# schematic.net
KiCad netlist of a schematic drawn in Altium Designer
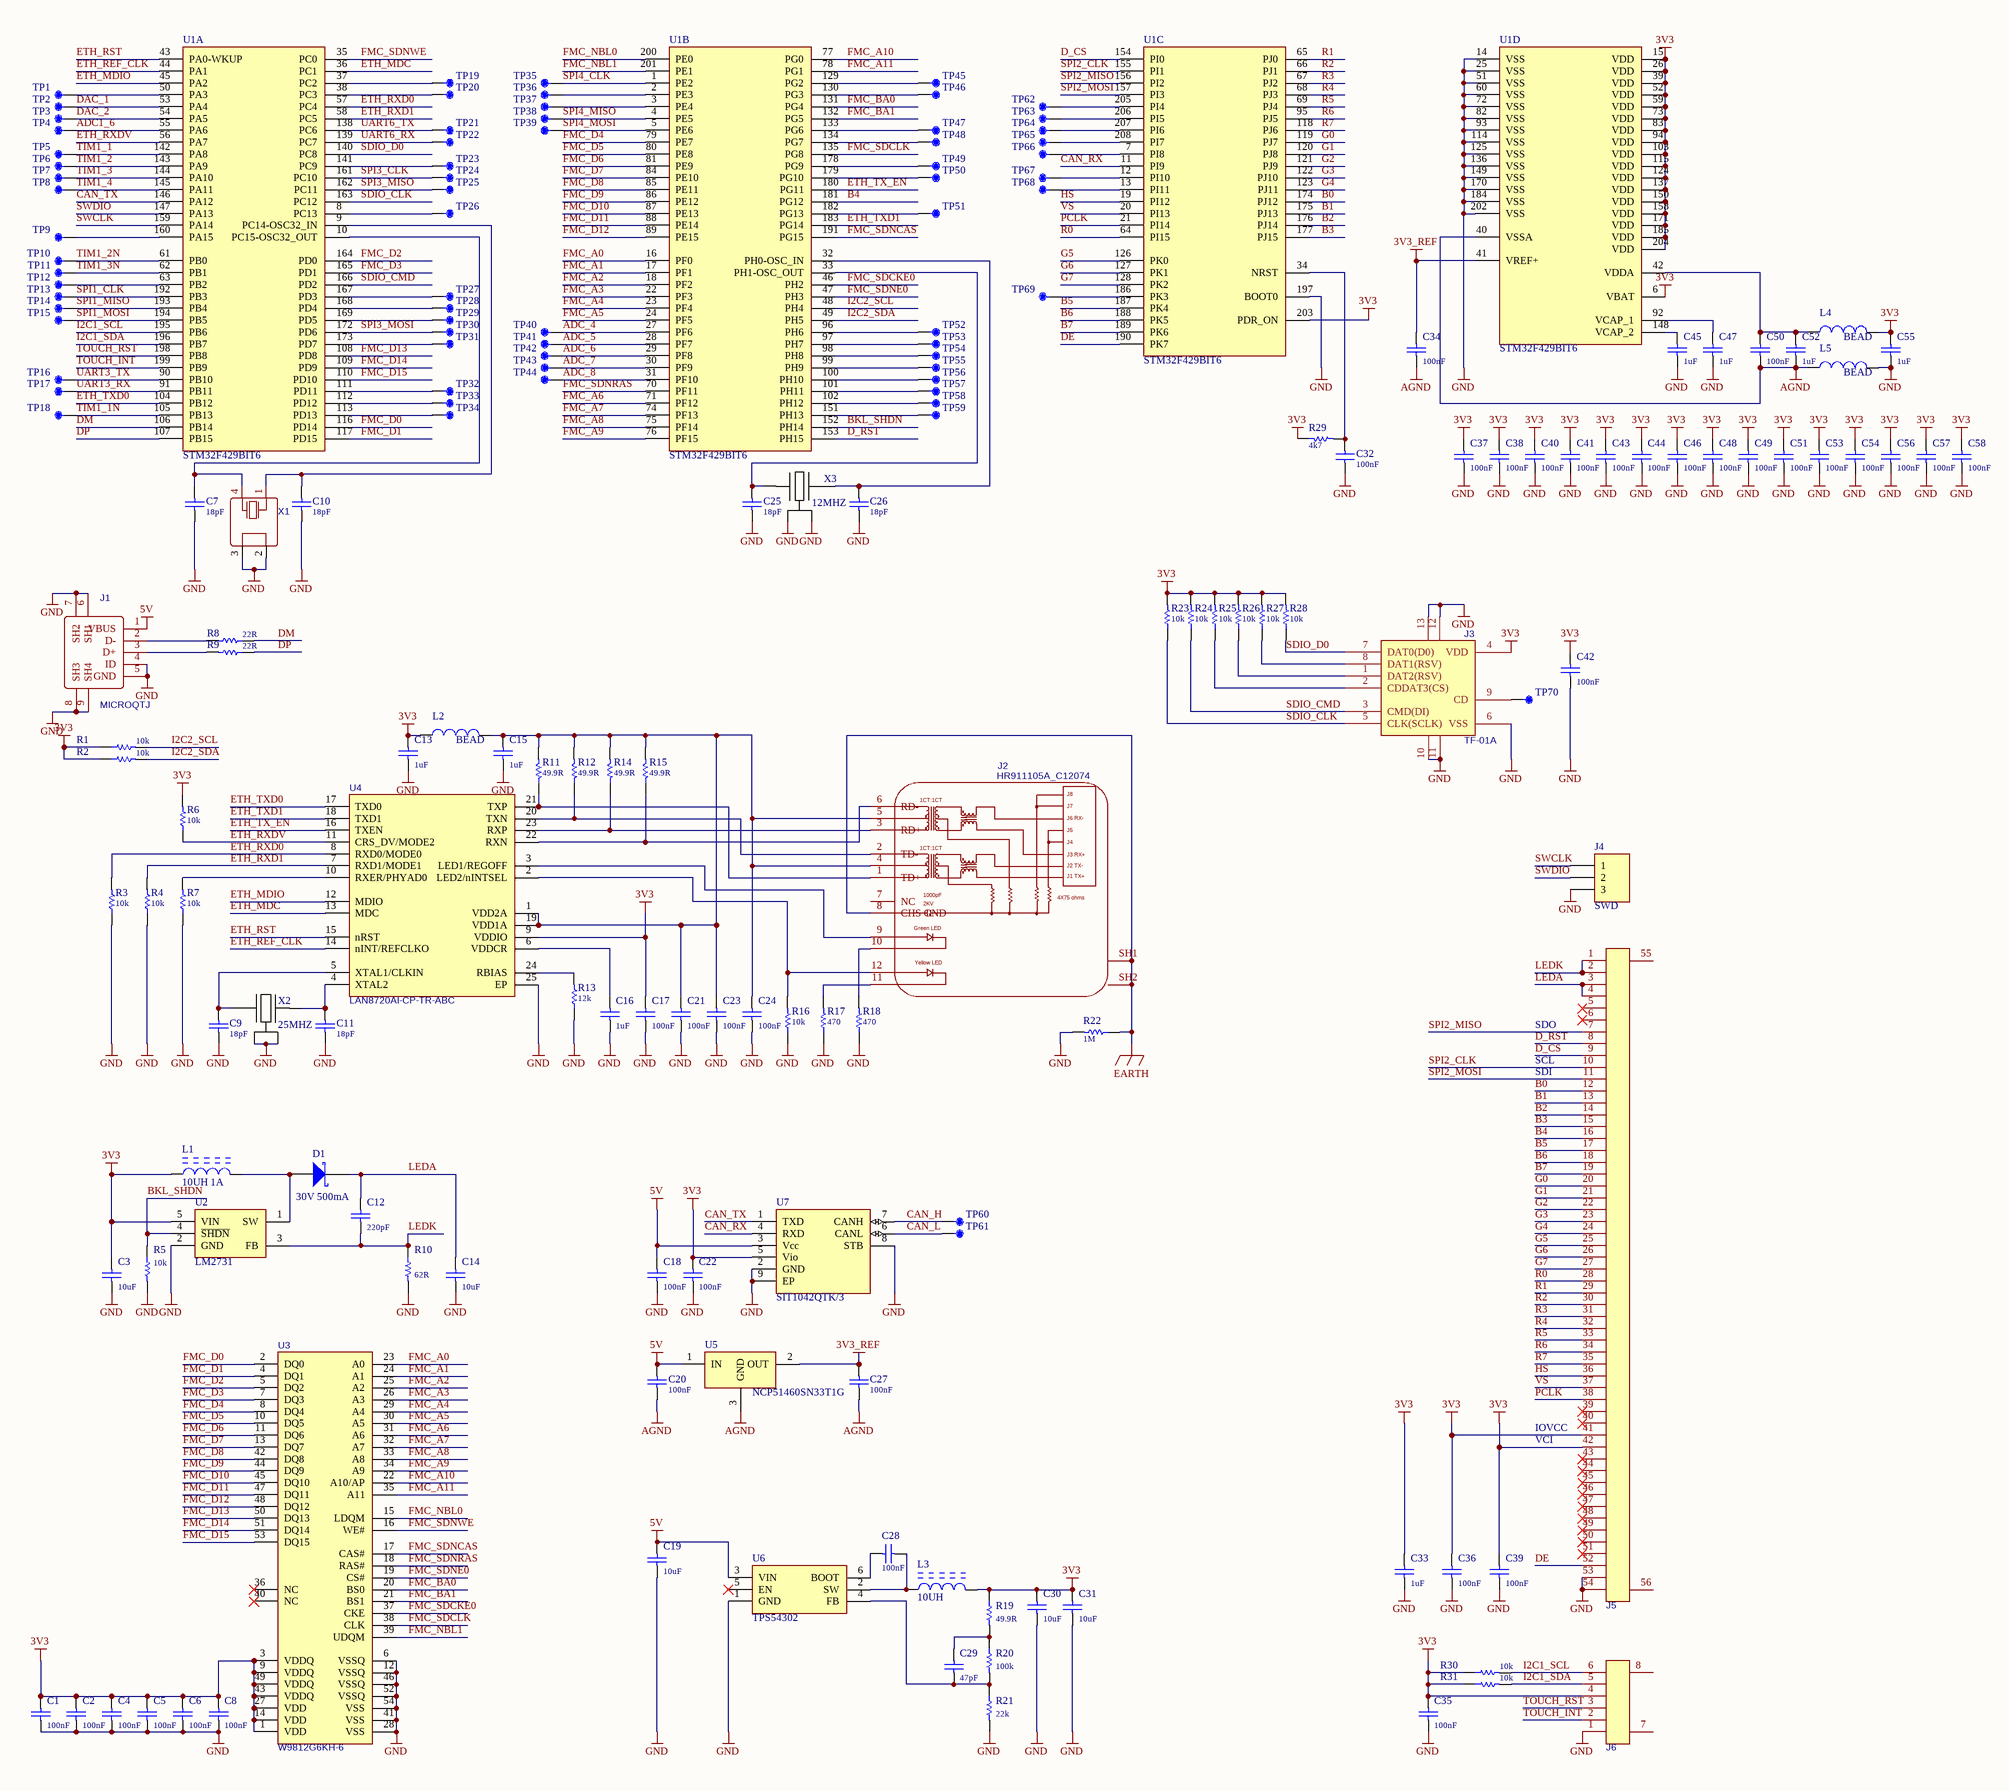
[diagram p0: schematic.SchDoc]

(export (version "E")
  (design (tool "Eeschema 10.0.6"))
  (components
    (comp (ref "C1")
      (value "100nF")
      (footprint "C0402")
      (description "100nF 0402")
      (libsource (lib "Miscellaneous Devices") (part "CAP"))
    )
    (comp (ref "C2")
      (value "100nF")
      (footprint "C0402")
      (description "100nF 0402")
      (libsource (lib "Miscellaneous Devices") (part "CAP"))
    )
    (comp (ref "C3")
      (value "10uF")
      (footprint "C0603")
      (description "10uF 0603")
      (libsource (lib "RR_Passive") (part "CAP"))
    )
    (comp (ref "C4")
      (value "100nF")
      (footprint "C0402")
      (description "100nF 0402")
      (libsource (lib "Miscellaneous Devices") (part "CAP"))
    )
    (comp (ref "C5")
      (value "100nF")
      (footprint "C0402")
      (description "100nF 0402")
      (libsource (lib "Miscellaneous Devices") (part "CAP"))
    )
    (comp (ref "C6")
      (value "100nF")
      (footprint "C0402")
      (description "100nF 0402")
      (libsource (lib "Miscellaneous Devices") (part "CAP"))
    )
    (comp (ref "C7")
      (value "18pF")
      (footprint "C0402")
      (description "18pF 0402")
      (libsource (lib "Miscellaneous Devices") (part "CAP"))
    )
    (comp (ref "C8")
      (value "100nF")
      (footprint "C0402")
      (description "100nF 0402")
      (libsource (lib "Miscellaneous Devices") (part "CAP"))
    )
    (comp (ref "C9")
      (value "18pF")
      (footprint "C0402")
      (description "18pF 0402")
      (libsource (lib "Miscellaneous Devices") (part "CAP"))
    )
    (comp (ref "C10")
      (value "18pF")
      (footprint "C0402")
      (description "18pF 0402")
      (libsource (lib "Miscellaneous Devices") (part "CAP"))
    )
    (comp (ref "C11")
      (value "18pF")
      (footprint "C0402")
      (description "18pF 0402")
      (libsource (lib "Miscellaneous Devices") (part "CAP"))
    )
    (comp (ref "C12")
      (value "220pF")
      (footprint "C0402")
      (description "220pF 0402")
      (libsource (lib "RR_Passive") (part "CAP"))
    )
    (comp (ref "C13")
      (value "1uF")
      (footprint "C0603")
      (description "1uF 0603")
      (libsource (lib "Miscellaneous Devices") (part "CAP"))
    )
    (comp (ref "C14")
      (value "10uF")
      (footprint "C1206")
      (description "10uF 1206")
      (libsource (lib "RR_Passive") (part "CAP"))
    )
    (comp (ref "C15")
      (value "1uF")
      (footprint "C0603")
      (description "1uF 0603")
      (libsource (lib "Miscellaneous Devices") (part "CAP"))
    )
    (comp (ref "C16")
      (value "1uF")
      (footprint "C0603")
      (description "1uF 0603")
      (libsource (lib "Miscellaneous Devices") (part "CAP"))
    )
    (comp (ref "C17")
      (value "100nF")
      (footprint "C0402")
      (description "100nF 0402")
      (libsource (lib "Miscellaneous Devices") (part "CAP"))
    )
    (comp (ref "C18")
      (value "100nF")
      (footprint "C0402")
      (description "100nF 0402")
      (libsource (lib "Miscellaneous Devices") (part "CAP"))
    )
    (comp (ref "C19")
      (value "10uF")
      (footprint "C1206")
      (description "10uF 1206")
      (libsource (lib "Miscellaneous Devices") (part "CAP"))
    )
    (comp (ref "C20")
      (value "100nF")
      (footprint "C0603")
      (description "100nf 0603")
      (libsource (lib "Miscellaneous Devices") (part "CAP"))
    )
    (comp (ref "C21")
      (value "100nF")
      (footprint "C0402")
      (description "100nF 0402")
      (libsource (lib "Miscellaneous Devices") (part "CAP"))
    )
    (comp (ref "C22")
      (value "100nF")
      (footprint "C0402")
      (description "100nF 0402")
      (libsource (lib "Miscellaneous Devices") (part "CAP"))
    )
    (comp (ref "C23")
      (value "100nF")
      (footprint "C0402")
      (description "100nF 0402")
      (libsource (lib "Miscellaneous Devices") (part "CAP"))
    )
    (comp (ref "C24")
      (value "100nF")
      (footprint "C0402")
      (description "100nF 0402")
      (libsource (lib "Miscellaneous Devices") (part "CAP"))
    )
    (comp (ref "C25")
      (value "18pF")
      (footprint "C0402")
      (description "18pF 0402")
      (libsource (lib "Miscellaneous Devices") (part "CAP"))
    )
    (comp (ref "C26")
      (value "18pF")
      (footprint "C0402")
      (description "18pF 0402")
      (libsource (lib "Miscellaneous Devices") (part "CAP"))
    )
    (comp (ref "C27")
      (value "100nF")
      (footprint "C0603")
      (description "100nF 0603")
      (libsource (lib "Miscellaneous Devices") (part "CAP"))
    )
    (comp (ref "C28")
      (value "100nF")
      (footprint "C0603")
      (description "100nF 0603")
      (libsource (lib "Miscellaneous Devices") (part "CAP"))
    )
    (comp (ref "C29")
      (value "47pF")
      (footprint "C0603")
      (description "47pF 0603")
      (libsource (lib "Miscellaneous Devices") (part "CAP"))
    )
    (comp (ref "C30")
      (value "10uF")
      (footprint "C1206")
      (description "10uF 1206")
      (libsource (lib "Miscellaneous Devices") (part "CAP"))
    )
    (comp (ref "C31")
      (value "10uF")
      (footprint "C1206")
      (description "10uF 1206")
      (libsource (lib "Miscellaneous Devices") (part "CAP"))
    )
    (comp (ref "C32")
      (value "100nF")
      (footprint "C0402")
      (description "100nF 0402")
      (libsource (lib "Miscellaneous Devices") (part "CAP"))
    )
    (comp (ref "C33")
      (value "1uF")
      (footprint "C0603")
      (description "1uF 0603")
      (libsource (lib "Miscellaneous Devices") (part "CAP"))
    )
    (comp (ref "C34")
      (value "100nF")
      (footprint "C0402")
      (description "100nF 0402")
      (libsource (lib "Miscellaneous Devices") (part "CAP"))
    )
    (comp (ref "C35")
      (value "100nF")
      (footprint "C0402")
      (description "100nF 0402")
      (libsource (lib "Miscellaneous Devices") (part "CAP"))
    )
    (comp (ref "C36")
      (value "100nF")
      (footprint "C0402")
      (description "100nF 0402")
      (libsource (lib "Miscellaneous Devices") (part "CAP"))
    )
    (comp (ref "C37")
      (value "100nF")
      (footprint "C0402")
      (description "100nF 0402")
      (libsource (lib "Miscellaneous Devices") (part "CAP"))
    )
    (comp (ref "C38")
      (value "100nF")
      (footprint "C0402")
      (description "100nF 0402")
      (libsource (lib "Miscellaneous Devices") (part "CAP"))
    )
    (comp (ref "C39")
      (value "100nF")
      (footprint "C0402")
      (description "100nF 0402")
      (libsource (lib "Miscellaneous Devices") (part "CAP"))
    )
    (comp (ref "C40")
      (value "100nF")
      (footprint "C0402")
      (description "100nF 0402")
      (libsource (lib "Miscellaneous Devices") (part "CAP"))
    )
    (comp (ref "C41")
      (value "100nF")
      (footprint "C0402")
      (description "100nF 0402")
      (libsource (lib "Miscellaneous Devices") (part "CAP"))
    )
    (comp (ref "C42")
      (value "100nF")
      (footprint "C0402")
      (description "100nF 0402")
      (libsource (lib "Miscellaneous Devices") (part "CAP"))
    )
    (comp (ref "C43")
      (value "100nF")
      (footprint "C0402")
      (description "100nF 0402")
      (libsource (lib "Miscellaneous Devices") (part "CAP"))
    )
    (comp (ref "C44")
      (value "100nF")
      (footprint "C0402")
      (description "100nF 0402")
      (libsource (lib "Miscellaneous Devices") (part "CAP"))
    )
    (comp (ref "C45")
      (value "1uF")
      (footprint "C0603")
      (description "1uF 0603")
      (libsource (lib "Miscellaneous Devices") (part "CAP"))
    )
    (comp (ref "C46")
      (value "100nF")
      (footprint "C0402")
      (description "100nF 0402")
      (libsource (lib "Miscellaneous Devices") (part "CAP"))
    )
    (comp (ref "C47")
      (value "1uF")
      (footprint "C0603")
      (description "1uF 0603")
      (libsource (lib "Miscellaneous Devices") (part "CAP"))
    )
    (comp (ref "C48")
      (value "100nF")
      (footprint "C0402")
      (description "100nF 0402")
      (libsource (lib "Miscellaneous Devices") (part "CAP"))
    )
    (comp (ref "C49")
      (value "100nF")
      (footprint "C0402")
      (description "100nF 0402")
      (libsource (lib "Miscellaneous Devices") (part "CAP"))
    )
    (comp (ref "C50")
      (value "100nF")
      (footprint "C0402")
      (description "100nF 0402")
      (libsource (lib "Miscellaneous Devices") (part "CAP"))
    )
    (comp (ref "C51")
      (value "100nF")
      (footprint "C0402")
      (description "100nF 0402")
      (libsource (lib "Miscellaneous Devices") (part "CAP"))
    )
    (comp (ref "C52")
      (value "1uF")
      (footprint "C0603")
      (description "1uF 0603")
      (libsource (lib "Miscellaneous Devices") (part "CAP"))
    )
    (comp (ref "C53")
      (value "100nF")
      (footprint "C0402")
      (description "100nF 0402")
      (libsource (lib "Miscellaneous Devices") (part "CAP"))
    )
    (comp (ref "C54")
      (value "100nF")
      (footprint "C0402")
      (description "100nF 0402")
      (libsource (lib "Miscellaneous Devices") (part "CAP"))
    )
    (comp (ref "C55")
      (value "1uF")
      (footprint "C0603")
      (description "1uF 0603")
      (libsource (lib "Miscellaneous Devices") (part "CAP"))
    )
    (comp (ref "C56")
      (value "100nF")
      (footprint "C0402")
      (description "100nF 0402")
      (libsource (lib "Miscellaneous Devices") (part "CAP"))
    )
    (comp (ref "C57")
      (value "100nF")
      (footprint "C0402")
      (description "100nF 0402")
      (libsource (lib "Miscellaneous Devices") (part "CAP"))
    )
    (comp (ref "C58")
      (value "100nF")
      (footprint "C0402")
      (description "100nF 0402")
      (libsource (lib "Miscellaneous Devices") (part "CAP"))
    )
    (comp (ref "D1")
      (value "30V 500mA")
      (footprint "SOD123")
      (description "1N4148WS")
      (libsource (lib "RozumLibrary") (part "MBR0530T1G"))
    )
    (comp (ref "J1")
      (value "MICROQTJ")
      (footprint "MICRO-USB-SMD_MICROQTJ")
      (libsource (lib "altium-import") (part "root_0_MICROQTJ_"))
    )
    (comp (ref "J2")
      (value "HR911105A_C12074")
      (footprint "RJ45-TH_HR911105A")
      (libsource (lib "altium-import") (part "root_0_HR911105A_C12074_"))
    )
    (comp (ref "J3") (value "TF-01A") (footprint "TF-SMD_TF-01A") (libsource (lib "Schlib1") (part "TF-01A")))
    (comp (ref "J4")
      (value "SWD")
      (footprint "SWD")
      (libsource (lib "Miscellaneous Devices") (part "Header 3"))
    )
    (comp (ref "J5")
      (value "KH-CL0.5-H2.0-54PIN")
      (footprint "FPC-SMD_KH-CL0.5-H2.0-54PIN")
      (libsource (lib "Schlib2") (part "KH-CL0.5-H2.0-54PIN"))
    )
    (comp (ref "J6")
      (value "KH-CL0.5-H2.0-6PS")
      (footprint "FPC-SMD_KH-CL0.5-H2.0-6PS")
      (libsource (lib "Schlib2") (part "KH-CL0.5-H2.0-6PS"))
    )
    (comp (ref "L1")
      (value "10UH 1A")
      (footprint "IND_SDE0403A_4X4MM")
      (description "VLS252012HBX-100M-1")
      (libsource (lib "RozumLibrary") (part "SRN3015-100M"))
    )
    (comp (ref "L2")
      (value "BEAD")
      (footprint "L0603")
      (description "BEAD 0402")
      (libsource (lib "Miscellaneous Devices") (part "BLM18AG601SN1D"))
    )
    (comp (ref "L3")
      (value "10UH")
      (footprint "L2520")
      (description "CYA0630-10UH")
      (libsource (lib "Miscellaneous Devices") (part "SRN3015-100M"))
    )
    (comp (ref "L4")
      (value "BEAD")
      (footprint "L0402")
      (description "BEAD 0402")
      (libsource (lib "Miscellaneous Devices") (part "BLM18AG601SN1D"))
    )
    (comp (ref "L5")
      (value "BEAD")
      (footprint "L0402")
      (description "BEAD 0402")
      (libsource (lib "Miscellaneous Devices") (part "BLM18AG601SN1D"))
    )
    (comp (ref "R1")
      (value "10k")
      (footprint "R0603")
      (description "10k 0603")
      (libsource (lib "RR_Passive") (part "RES"))
    )
    (comp (ref "R2")
      (value "10k")
      (footprint "R0603")
      (description "10k 0603")
      (libsource (lib "RR_Passive") (part "RES"))
    )
    (comp (ref "R3")
      (value "10k")
      (footprint "R0402")
      (description "10k 0402")
      (libsource (lib "RR_Passive") (part "RES"))
    )
    (comp (ref "R4")
      (value "10k")
      (footprint "R0402")
      (description "10k 0402")
      (libsource (lib "RR_Passive") (part "RES"))
    )
    (comp (ref "R5")
      (value "10k")
      (footprint "R0402")
      (description "10k 0402")
      (libsource (lib "RR_Passive") (part "RES"))
    )
    (comp (ref "R6")
      (value "10k")
      (footprint "R0402")
      (description "10k 0402")
      (libsource (lib "RR_Passive") (part "RES"))
    )
    (comp (ref "R7")
      (value "10k")
      (footprint "R0402")
      (description "10k 0402")
      (libsource (lib "RR_Passive") (part "RES"))
    )
    (comp (ref "R8")
      (value "22R")
      (footprint "R0603")
      (description "22R 0603")
      (libsource (lib "Miscellaneous Devices") (part "RES"))
    )
    (comp (ref "R9")
      (value "22R")
      (footprint "R0603")
      (description "22R 0603")
      (libsource (lib "Miscellaneous Devices") (part "RES"))
    )
    (comp (ref "R10")
      (value "62R")
      (footprint "R0603")
      (description "62R 0603")
      (libsource (lib "RR_Passive") (part "RES"))
    )
    (comp (ref "R11")
      (value "49.9R")
      (footprint "R0603")
      (description "49.9R 0603")
      (libsource (lib "Miscellaneous Devices") (part "RES"))
    )
    (comp (ref "R12")
      (value "49.9R")
      (footprint "R0603")
      (description "49.9R 0603")
      (libsource (lib "Miscellaneous Devices") (part "RES"))
    )
    (comp (ref "R13")
      (value "12k")
      (footprint "R0402")
      (description "12k 0402")
      (libsource (lib "Miscellaneous Devices") (part "RES"))
    )
    (comp (ref "R14")
      (value "49.9R")
      (footprint "R0603")
      (description "49.9R 0603")
      (libsource (lib "Miscellaneous Devices") (part "RES"))
    )
    (comp (ref "R15")
      (value "49.9R")
      (footprint "R0603")
      (description "49.9R 0603")
      (libsource (lib "Miscellaneous Devices") (part "RES"))
    )
    (comp (ref "R16")
      (value "10k")
      (footprint "R0603")
      (description "10k 0603")
      (libsource (lib "RR_Passive") (part "RES"))
    )
    (comp (ref "R17")
      (value "470")
      (footprint "R0603")
      (description "470R 0603")
      (libsource (lib "RR_Passive") (part "RES"))
    )
    (comp (ref "R18")
      (value "470")
      (footprint "R0603")
      (description "470R 0603")
      (libsource (lib "RR_Passive") (part "RES"))
    )
    (comp (ref "R19")
      (value "49.9R")
      (footprint "R0603")
      (description "49.9R 0603")
      (libsource (lib "") (part "RES_1"))
    )
    (comp (ref "R20")
      (value "100k")
      (footprint "R0603")
      (description "100k 0603")
      (libsource (lib "Miscellaneous Devices") (part "RES"))
    )
    (comp (ref "R21")
      (value "22k")
      (footprint "R0603")
      (description "22k 0603")
      (libsource (lib "Miscellaneous Devices") (part "RES"))
    )
    (comp (ref "R22")
      (value "1M")
      (footprint "R1206")
      (description "1M 0603")
      (libsource (lib "RR_Passive") (part "RES"))
    )
    (comp (ref "R23")
      (value "10k")
      (footprint "R0603")
      (description "10k 0603")
      (libsource (lib "RR_Passive") (part "RES"))
    )
    (comp (ref "R24")
      (value "10k")
      (footprint "R0603")
      (description "10k 0603")
      (libsource (lib "RR_Passive") (part "RES"))
    )
    (comp (ref "R25")
      (value "10k")
      (footprint "R0603")
      (description "10k 0603")
      (libsource (lib "RR_Passive") (part "RES"))
    )
    (comp (ref "R26")
      (value "10k")
      (footprint "R0603")
      (description "10k 0603")
      (libsource (lib "RR_Passive") (part "RES"))
    )
    (comp (ref "R27")
      (value "10k")
      (footprint "R0603")
      (description "10k 0603")
      (libsource (lib "RR_Passive") (part "RES"))
    )
    (comp (ref "R28")
      (value "10k")
      (footprint "R0603")
      (description "10k 0603")
      (libsource (lib "RR_Passive") (part "RES"))
    )
    (comp (ref "R29")
      (value "4k7")
      (footprint "R0402")
      (description "4k7 0402")
      (libsource (lib "Miscellaneous Devices") (part "RES"))
    )
    (comp (ref "R30")
      (value "10k")
      (footprint "R0603")
      (description "10k 0603")
      (libsource (lib "RR_Passive") (part "RES"))
    )
    (comp (ref "R31")
      (value "10k")
      (footprint "R0603")
      (description "10k 0603")
      (libsource (lib "RR_Passive") (part "RES"))
    )
    (comp (ref "TP1")
      (value "~")
      (footprint "TP2030_SMD")
      (libsource (lib "Miscellaneous Devices") (part "TP_Dup1"))
    )
    (comp (ref "TP2")
      (value "~")
      (footprint "TP2030_SMD")
      (libsource (lib "Miscellaneous Devices") (part "TP_Dup1"))
    )
    (comp (ref "TP3")
      (value "~")
      (footprint "TP2030_SMD")
      (libsource (lib "Miscellaneous Devices") (part "TP_Dup1"))
    )
    (comp (ref "TP4")
      (value "~")
      (footprint "TP2030_SMD")
      (libsource (lib "Miscellaneous Devices") (part "TP_Dup1"))
    )
    (comp (ref "TP5")
      (value "~")
      (footprint "TP2030_SMD")
      (libsource (lib "Miscellaneous Devices") (part "TP_Dup1"))
    )
    (comp (ref "TP6")
      (value "~")
      (footprint "TP2030_SMD")
      (libsource (lib "Miscellaneous Devices") (part "TP_Dup1"))
    )
    (comp (ref "TP7")
      (value "~")
      (footprint "TP2030_SMD")
      (libsource (lib "Miscellaneous Devices") (part "TP_Dup1"))
    )
    (comp (ref "TP8")
      (value "~")
      (footprint "TP2030_SMD")
      (libsource (lib "Miscellaneous Devices") (part "TP_Dup1"))
    )
    (comp (ref "TP9")
      (value "~")
      (footprint "TP2030_SMD")
      (libsource (lib "Miscellaneous Devices") (part "TP_Dup1"))
    )
    (comp (ref "TP10")
      (value "~")
      (footprint "TP2030_SMD")
      (libsource (lib "Miscellaneous Devices") (part "TP_Dup1"))
    )
    (comp (ref "TP11")
      (value "~")
      (footprint "TP2030_SMD")
      (libsource (lib "Miscellaneous Devices") (part "TP_Dup1"))
    )
    (comp (ref "TP12")
      (value "~")
      (footprint "TP2030_SMD")
      (libsource (lib "Miscellaneous Devices") (part "TP_Dup1"))
    )
    (comp (ref "TP13")
      (value "~")
      (footprint "TP2030_SMD")
      (libsource (lib "Miscellaneous Devices") (part "TP_Dup1"))
    )
    (comp (ref "TP14")
      (value "~")
      (footprint "TP2030_SMD")
      (libsource (lib "Miscellaneous Devices") (part "TP_Dup1"))
    )
    (comp (ref "TP15")
      (value "~")
      (footprint "TP2030_SMD")
      (libsource (lib "Miscellaneous Devices") (part "TP_Dup1"))
    )
    (comp (ref "TP16")
      (value "~")
      (footprint "TP2030_SMD")
      (libsource (lib "Miscellaneous Devices") (part "TP_Dup1"))
    )
    (comp (ref "TP17")
      (value "~")
      (footprint "TP2030_SMD")
      (libsource (lib "Miscellaneous Devices") (part "TP_Dup1"))
    )
    (comp (ref "TP18")
      (value "~")
      (footprint "TP2030_SMD")
      (libsource (lib "Miscellaneous Devices") (part "TP_Dup1"))
    )
    (comp (ref "TP19")
      (value "~")
      (footprint "TP2030_SMD")
      (libsource (lib "Miscellaneous Devices") (part "TP_Dup1"))
    )
    (comp (ref "TP20")
      (value "~")
      (footprint "TP2030_SMD")
      (libsource (lib "Miscellaneous Devices") (part "TP_Dup1"))
    )
    (comp (ref "TP21")
      (value "~")
      (footprint "TP2030_SMD")
      (libsource (lib "Miscellaneous Devices") (part "TP_Dup1"))
    )
    (comp (ref "TP22")
      (value "~")
      (footprint "TP2030_SMD")
      (libsource (lib "Miscellaneous Devices") (part "TP_Dup1"))
    )
    (comp (ref "TP23")
      (value "~")
      (footprint "TP2030_SMD")
      (libsource (lib "Miscellaneous Devices") (part "TP_Dup1"))
    )
    (comp (ref "TP24")
      (value "~")
      (footprint "TP2030_SMD")
      (libsource (lib "Miscellaneous Devices") (part "TP_Dup1"))
    )
    (comp (ref "TP25")
      (value "~")
      (footprint "TP2030_SMD")
      (libsource (lib "Miscellaneous Devices") (part "TP_Dup1"))
    )
    (comp (ref "TP26")
      (value "~")
      (footprint "TP2030_SMD")
      (libsource (lib "Miscellaneous Devices") (part "TP_Dup1"))
    )
    (comp (ref "TP27")
      (value "~")
      (footprint "TP2030_SMD")
      (libsource (lib "Miscellaneous Devices") (part "TP_Dup1"))
    )
    (comp (ref "TP28")
      (value "~")
      (footprint "TP2030_SMD")
      (libsource (lib "Miscellaneous Devices") (part "TP_Dup1"))
    )
    (comp (ref "TP29")
      (value "~")
      (footprint "TP2030_SMD")
      (libsource (lib "Miscellaneous Devices") (part "TP_Dup1"))
    )
    (comp (ref "TP30")
      (value "~")
      (footprint "TP2030_SMD")
      (libsource (lib "Miscellaneous Devices") (part "TP_Dup1"))
    )
    (comp (ref "TP31")
      (value "~")
      (footprint "TP2030_SMD")
      (libsource (lib "Miscellaneous Devices") (part "TP_Dup1"))
    )
    (comp (ref "TP32")
      (value "~")
      (footprint "TP2030_SMD")
      (libsource (lib "Miscellaneous Devices") (part "TP_Dup1"))
    )
    (comp (ref "TP33")
      (value "~")
      (footprint "TP2030_SMD")
      (libsource (lib "Miscellaneous Devices") (part "TP_Dup1"))
    )
    (comp (ref "TP34")
      (value "~")
      (footprint "TP2030_SMD")
      (libsource (lib "Miscellaneous Devices") (part "TP_Dup1"))
    )
    (comp (ref "TP35")
      (value "~")
      (footprint "TP2030_SMD")
      (libsource (lib "Miscellaneous Devices") (part "TP_Dup1"))
    )
    (comp (ref "TP36")
      (value "~")
      (footprint "TP2030_SMD")
      (libsource (lib "Miscellaneous Devices") (part "TP_Dup1"))
    )
    (comp (ref "TP37")
      (value "~")
      (footprint "TP2030_SMD")
      (libsource (lib "Miscellaneous Devices") (part "TP_Dup1"))
    )
    (comp (ref "TP38")
      (value "~")
      (footprint "TP2030_SMD")
      (libsource (lib "Miscellaneous Devices") (part "TP_Dup1"))
    )
    (comp (ref "TP39")
      (value "~")
      (footprint "TP2030_SMD")
      (libsource (lib "Miscellaneous Devices") (part "TP_Dup1"))
    )
    (comp (ref "TP40")
      (value "~")
      (footprint "TP2030_SMD")
      (libsource (lib "Miscellaneous Devices") (part "TP_Dup1"))
    )
    (comp (ref "TP41")
      (value "~")
      (footprint "TP2030_SMD")
      (libsource (lib "Miscellaneous Devices") (part "TP_Dup1"))
    )
    (comp (ref "TP42")
      (value "~")
      (footprint "TP2030_SMD")
      (libsource (lib "Miscellaneous Devices") (part "TP_Dup1"))
    )
    (comp (ref "TP43")
      (value "~")
      (footprint "TP2030_SMD")
      (libsource (lib "Miscellaneous Devices") (part "TP_Dup1"))
    )
    (comp (ref "TP44")
      (value "~")
      (footprint "TP2030_SMD")
      (libsource (lib "Miscellaneous Devices") (part "TP_Dup1"))
    )
    (comp (ref "TP45")
      (value "~")
      (footprint "TP2030_SMD")
      (libsource (lib "Miscellaneous Devices") (part "TP_Dup1"))
    )
    (comp (ref "TP46")
      (value "~")
      (footprint "TP2030_SMD")
      (libsource (lib "Miscellaneous Devices") (part "TP_Dup1"))
    )
    (comp (ref "TP47")
      (value "~")
      (footprint "TP2030_SMD")
      (libsource (lib "Miscellaneous Devices") (part "TP_Dup1"))
    )
    (comp (ref "TP48")
      (value "~")
      (footprint "TP2030_SMD")
      (libsource (lib "Miscellaneous Devices") (part "TP_Dup1"))
    )
    (comp (ref "TP49")
      (value "~")
      (footprint "TP2030_SMD")
      (libsource (lib "Miscellaneous Devices") (part "TP_Dup1"))
    )
    (comp (ref "TP50")
      (value "~")
      (footprint "TP2030_SMD")
      (libsource (lib "Miscellaneous Devices") (part "TP_Dup1"))
    )
    (comp (ref "TP51")
      (value "~")
      (footprint "TP2030_SMD")
      (libsource (lib "Miscellaneous Devices") (part "TP_Dup1"))
    )
    (comp (ref "TP52")
      (value "~")
      (footprint "TP2030_SMD")
      (libsource (lib "Miscellaneous Devices") (part "TP_Dup1"))
    )
    (comp (ref "TP53")
      (value "~")
      (footprint "TP2030_SMD")
      (libsource (lib "Miscellaneous Devices") (part "TP_Dup1"))
    )
    (comp (ref "TP54")
      (value "~")
      (footprint "TP2030_SMD")
      (libsource (lib "Miscellaneous Devices") (part "TP_Dup1"))
    )
    (comp (ref "TP55")
      (value "~")
      (footprint "TP2030_SMD")
      (libsource (lib "Miscellaneous Devices") (part "TP_Dup1"))
    )
    (comp (ref "TP56")
      (value "~")
      (footprint "TP2030_SMD")
      (libsource (lib "Miscellaneous Devices") (part "TP_Dup1"))
    )
    (comp (ref "TP57")
      (value "~")
      (footprint "TP2030_SMD")
      (libsource (lib "Miscellaneous Devices") (part "TP_Dup1"))
    )
    (comp (ref "TP58")
      (value "~")
      (footprint "TP2030_SMD")
      (libsource (lib "Miscellaneous Devices") (part "TP_Dup1"))
    )
    (comp (ref "TP59")
      (value "~")
      (footprint "TP2030_SMD")
      (libsource (lib "Miscellaneous Devices") (part "TP_Dup1"))
    )
    (comp (ref "TP60")
      (value "~")
      (footprint "TP2030_SMD")
      (libsource (lib "Miscellaneous Devices") (part "TP_Dup1"))
    )
    (comp (ref "TP61")
      (value "~")
      (footprint "TP2030_SMD")
      (libsource (lib "Miscellaneous Devices") (part "TP_Dup1"))
    )
    (comp (ref "TP62")
      (value "~")
      (footprint "TP2030_SMD")
      (libsource (lib "Miscellaneous Devices") (part "TP_Dup1"))
    )
    (comp (ref "TP63")
      (value "~")
      (footprint "TP2030_SMD")
      (libsource (lib "Miscellaneous Devices") (part "TP_Dup1"))
    )
    (comp (ref "TP64")
      (value "~")
      (footprint "TP2030_SMD")
      (libsource (lib "Miscellaneous Devices") (part "TP_Dup1"))
    )
    (comp (ref "TP65")
      (value "~")
      (footprint "TP2030_SMD")
      (libsource (lib "Miscellaneous Devices") (part "TP_Dup1"))
    )
    (comp (ref "TP66")
      (value "~")
      (footprint "TP2030_SMD")
      (libsource (lib "Miscellaneous Devices") (part "TP_Dup1"))
    )
    (comp (ref "TP67")
      (value "~")
      (footprint "TP2030_SMD")
      (libsource (lib "Miscellaneous Devices") (part "TP_Dup1"))
    )
    (comp (ref "TP68")
      (value "~")
      (footprint "TP2030_SMD")
      (libsource (lib "Miscellaneous Devices") (part "TP_Dup1"))
    )
    (comp (ref "TP69")
      (value "~")
      (footprint "TP2030_SMD")
      (libsource (lib "Miscellaneous Devices") (part "TP_Dup1"))
    )
    (comp (ref "TP70")
      (value "~")
      (footprint "TP2030_SMD")
      (libsource (lib "Miscellaneous Devices") (part "TP_Dup1"))
    )
    (comp (ref "U1")
      (value "STM32F429BIT6")
      (footprint "LQFP-208_L28.0-W28.0-P0.50-BL")
      (libsource (lib "Schlib1") (part "STM32F429BIT6"))
    )
    (comp (ref "U2")
      (value "LM2731")
      (footprint "SOT-23-5")
      (description "IC REG BOOST ADJ 800MA SOT23-5")
      (libsource (lib "RozumLibrary") (part "LM27313XMFX"))
    )
    (comp (ref "U3")
      (value "W9812G6KH-6")
      (footprint "TSOP-54_L22.2-W10.2-P0.80-LS11.8-BL")
      (libsource (lib "Schlib1") (part "W9812G6KH-6"))
    )
    (comp (ref "U4")
      (value "LAN8720AI-CP-TR-ABC")
      (footprint "QFN-24_L4.0-W4.0-P0.50-TL-EP2.5")
      (libsource (lib "Schlib1") (part "LAN8720AI-CP-TR-ABC"))
    )
    (comp (ref "U5")
      (value "NCP51460SN33T1G")
      (footprint "SOT-23")
      (libsource (lib "Schlib1") (part "NCP51460SN33T1G"))
    )
    (comp (ref "U6")
      (value "TPS54302")
      (footprint "SOT-23-6")
      (description "TPS54302DDCR")
      (libsource (lib "Miscellaneous Devices") (part "LM27313XMFX"))
    )
    (comp (ref "U7")
      (value "SIT1042QTK/3")
      (footprint "DFN8_3X3_P065")
      (libsource (lib "Miscellaneous Devices") (part "LTC2875"))
    )
    (comp (ref "X1") (value "32.768kHz") (footprint "MC-146") (libsource (lib "Schlib1") (part "32.768kHz")))
    (comp (ref "X2")
      (value "25MHZ")
      (footprint "CRYSTAL_3.2x2.5mm")
      (description "X322525MOB4SI")
      (libsource (lib "Miscellaneous Devices") (part "CRYSTAL 12MHZ 3.20mm x 2.50mm"))
    )
    (comp (ref "X3")
      (value "12MHZ")
      (footprint "CRYSTAL_3.2x2.5mm")
      (description "X322512MOB4SI")
      (libsource (lib "Miscellaneous Devices") (part "CRYSTAL 12MHZ 3.20mm x 2.50mm"))
    )
  )
  (nets
    (net (code "1") (name "/ADC1_6") (class "Default")
      (node (ref "TP4") (pin "1") (pinfunction "1_1") (pintype "passive"))
      (node (ref "U1") (pin "55") (pinfunction "PA6_55") (pintype "passive"))
    )
    (net (code "2") (name "/ADC_4") (class "Default")
      (node (ref "TP40") (pin "1") (pinfunction "1_1") (pintype "passive"))
      (node (ref "U1") (pin "27") (pinfunction "PF6_27") (pintype "passive"))
    )
    (net (code "3") (name "/ADC_5") (class "Default")
      (node (ref "TP41") (pin "1") (pinfunction "1_1") (pintype "passive"))
      (node (ref "U1") (pin "28") (pinfunction "PF7_28") (pintype "passive"))
    )
    (net (code "4") (name "/ADC_6") (class "Default")
      (node (ref "TP42") (pin "1") (pinfunction "1_1") (pintype "passive"))
      (node (ref "U1") (pin "29") (pinfunction "PF8_29") (pintype "passive"))
    )
    (net (code "5") (name "/ADC_7") (class "Default")
      (node (ref "TP43") (pin "1") (pinfunction "1_1") (pintype "passive"))
      (node (ref "U1") (pin "30") (pinfunction "PF9_30") (pintype "passive"))
    )
    (net (code "6") (name "/ADC_8") (class "Default")
      (node (ref "TP44") (pin "1") (pinfunction "1_1") (pintype "passive"))
      (node (ref "U1") (pin "31") (pinfunction "PF10_31") (pintype "passive"))
    )
    (net (code "7") (name "/B0") (class "Default")
      (node (ref "J5") (pin "12") (pinfunction "12_12") (pintype "passive"))
      (node (ref "U1") (pin "174") (pinfunction "PJ12_174") (pintype "passive"))
    )
    (net (code "8") (name "/B1") (class "Default")
      (node (ref "J5") (pin "13") (pinfunction "13_13") (pintype "passive"))
      (node (ref "U1") (pin "175") (pinfunction "PJ13_175") (pintype "passive"))
    )
    (net (code "9") (name "/B2") (class "Default")
      (node (ref "J5") (pin "14") (pinfunction "14_14") (pintype "passive"))
      (node (ref "U1") (pin "176") (pinfunction "PJ14_176") (pintype "passive"))
    )
    (net (code "10") (name "/B3") (class "Default")
      (node (ref "J5") (pin "15") (pinfunction "15_15") (pintype "passive"))
      (node (ref "U1") (pin "177") (pinfunction "PJ15_177") (pintype "passive"))
    )
    (net (code "11") (name "/B4") (class "Default")
      (node (ref "J5") (pin "16") (pinfunction "16_16") (pintype "passive"))
      (node (ref "U1") (pin "181") (pinfunction "PG12_181") (pintype "passive"))
    )
    (net (code "12") (name "/B5") (class "Default")
      (node (ref "J5") (pin "17") (pinfunction "17_17") (pintype "passive"))
      (node (ref "U1") (pin "187") (pinfunction "PK4_187") (pintype "passive"))
    )
    (net (code "13") (name "/B6") (class "Default")
      (node (ref "J5") (pin "18") (pinfunction "18_18") (pintype "passive"))
      (node (ref "U1") (pin "188") (pinfunction "PK5_188") (pintype "passive"))
    )
    (net (code "14") (name "/B7") (class "Default")
      (node (ref "J5") (pin "19") (pinfunction "19_19") (pintype "passive"))
      (node (ref "U1") (pin "189") (pinfunction "PK6_189") (pintype "passive"))
    )
    (net (code "15") (name "/BKL_SHDN") (class "Default")
      (node (ref "R5") (pin "1") (pinfunction "1_1") (pintype "passive"))
      (node (ref "U1") (pin "152") (pinfunction "PH14_152") (pintype "passive"))
      (node (ref "U2") (pin "4") (pinfunction "~{SHDN}_4") (pintype "passive"))
    )
    (net (code "16") (name "/CAN_H") (class "Default")
      (node (ref "TP60") (pin "1") (pinfunction "1_1") (pintype "passive"))
      (node (ref "U7") (pin "7") (pinfunction "CANH_7") (pintype "bidirectional"))
    )
    (net (code "17") (name "/CAN_L") (class "Default")
      (node (ref "TP61") (pin "1") (pinfunction "1_1") (pintype "passive"))
      (node (ref "U7") (pin "6") (pinfunction "CANL_6") (pintype "bidirectional"))
    )
    (net (code "18") (name "/CAN_RX") (class "Default")
      (node (ref "U1") (pin "11") (pinfunction "PI9_11") (pintype "passive"))
      (node (ref "U7") (pin "4") (pinfunction "RXD_4") (pintype "passive"))
    )
    (net (code "19") (name "/CAN_TX") (class "Default")
      (node (ref "U1") (pin "146") (pinfunction "PA12_146") (pintype "passive"))
      (node (ref "U7") (pin "1") (pinfunction "TXD_1") (pintype "passive"))
    )
    (net (code "20") (name "/DAC_1") (class "Default")
      (node (ref "TP2") (pin "1") (pinfunction "1_1") (pintype "passive"))
      (node (ref "U1") (pin "53") (pinfunction "PA4_53") (pintype "passive"))
    )
    (net (code "21") (name "/DAC_2") (class "Default")
      (node (ref "TP3") (pin "1") (pinfunction "1_1") (pintype "passive"))
      (node (ref "U1") (pin "54") (pinfunction "PA5_54") (pintype "passive"))
    )
    (net (code "22") (name "/DE") (class "Default")
      (node (ref "J5") (pin "52") (pinfunction "52_52") (pintype "passive"))
      (node (ref "U1") (pin "190") (pinfunction "PK7_190") (pintype "passive"))
    )
    (net (code "23") (name "/DM") (class "Default")
      (node (ref "R8") (pin "1") (pinfunction "1_1") (pintype "passive"))
      (node (ref "U1") (pin "106") (pinfunction "PB14_106") (pintype "passive"))
    )
    (net (code "24") (name "/DP") (class "Default")
      (node (ref "R9") (pin "1") (pinfunction "1_1") (pintype "passive"))
      (node (ref "U1") (pin "107") (pinfunction "PB15_107") (pintype "passive"))
    )
    (net (code "25") (name "/D_CS") (class "Default")
      (node (ref "J5") (pin "9") (pinfunction "9_9") (pintype "passive"))
      (node (ref "U1") (pin "154") (pinfunction "PI0_154") (pintype "passive"))
    )
    (net (code "26") (name "/D_RST") (class "Default")
      (node (ref "J5") (pin "8") (pinfunction "8_8") (pintype "passive"))
      (node (ref "U1") (pin "153") (pinfunction "PH15_153") (pintype "passive"))
    )
    (net (code "27") (name "/ETH_MDC") (class "Default")
      (node (ref "U1") (pin "36") (pinfunction "PC1_36") (pintype "passive"))
      (node (ref "U4") (pin "13") (pinfunction "MDC_13") (pintype "passive"))
    )
    (net (code "28") (name "/ETH_MDIO") (class "Default")
      (node (ref "U1") (pin "45") (pinfunction "PA2_45") (pintype "passive"))
      (node (ref "U4") (pin "12") (pinfunction "MDIO_12") (pintype "passive"))
    )
    (net (code "29") (name "/ETH_REF_CLK") (class "Default")
      (node (ref "U1") (pin "44") (pinfunction "PA1_44") (pintype "passive"))
      (node (ref "U4") (pin "14") (pinfunction "nINT/REFCLKO_14") (pintype "passive"))
    )
    (net (code "30") (name "/ETH_RST") (class "Default")
      (node (ref "U1") (pin "43") (pinfunction "PA0-WKUP_43") (pintype "passive"))
      (node (ref "U4") (pin "15") (pinfunction "nRST_15") (pintype "passive"))
    )
    (net (code "31") (name "/ETH_RXD0") (class "Default")
      (node (ref "R3") (pin "2") (pinfunction "2_2") (pintype "passive"))
      (node (ref "U1") (pin "57") (pinfunction "PC4_57") (pintype "passive"))
      (node (ref "U4") (pin "8") (pinfunction "RXD0/MODE0_8") (pintype "passive"))
    )
    (net (code "32") (name "/ETH_RXD1") (class "Default")
      (node (ref "R4") (pin "2") (pinfunction "2_2") (pintype "passive"))
      (node (ref "U1") (pin "58") (pinfunction "PC5_58") (pintype "passive"))
      (node (ref "U4") (pin "7") (pinfunction "RXD1/MODE1_7") (pintype "passive"))
    )
    (net (code "33") (name "/ETH_RXDV") (class "Default")
      (node (ref "R6") (pin "1") (pinfunction "1_1") (pintype "passive"))
      (node (ref "U1") (pin "56") (pinfunction "PA7_56") (pintype "passive"))
      (node (ref "U4") (pin "11") (pinfunction "CRS_DV/MODE2_11") (pintype "passive"))
    )
    (net (code "34") (name "/ETH_TXD0") (class "Default")
      (node (ref "U1") (pin "104") (pinfunction "PB12_104") (pintype "passive"))
      (node (ref "U4") (pin "17") (pinfunction "TXD0_17") (pintype "passive"))
    )
    (net (code "35") (name "/ETH_TXD1") (class "Default")
      (node (ref "U1") (pin "183") (pinfunction "PG14_183") (pintype "passive"))
      (node (ref "U4") (pin "18") (pinfunction "TXD1_18") (pintype "passive"))
    )
    (net (code "36") (name "/ETH_TX_EN") (class "Default")
      (node (ref "U1") (pin "180") (pinfunction "PG11_180") (pintype "passive"))
      (node (ref "U4") (pin "16") (pinfunction "TXEN_16") (pintype "passive"))
    )
    (net (code "37") (name "/FMC_A0") (class "Default")
      (node (ref "U1") (pin "16") (pinfunction "PF0_16") (pintype "passive"))
      (node (ref "U3") (pin "23") (pinfunction "A0_23") (pintype "passive"))
    )
    (net (code "38") (name "/FMC_A1") (class "Default")
      (node (ref "U1") (pin "17") (pinfunction "PF1_17") (pintype "passive"))
      (node (ref "U3") (pin "24") (pinfunction "A1_24") (pintype "passive"))
    )
    (net (code "39") (name "/FMC_A2") (class "Default")
      (node (ref "U1") (pin "18") (pinfunction "PF2_18") (pintype "passive"))
      (node (ref "U3") (pin "25") (pinfunction "A2_25") (pintype "passive"))
    )
    (net (code "40") (name "/FMC_A3") (class "Default")
      (node (ref "U1") (pin "22") (pinfunction "PF3_22") (pintype "passive"))
      (node (ref "U3") (pin "26") (pinfunction "A3_26") (pintype "passive"))
    )
    (net (code "41") (name "/FMC_A4") (class "Default")
      (node (ref "U1") (pin "23") (pinfunction "PF4_23") (pintype "passive"))
      (node (ref "U3") (pin "29") (pinfunction "A4_29") (pintype "passive"))
    )
    (net (code "42") (name "/FMC_A5") (class "Default")
      (node (ref "U1") (pin "24") (pinfunction "PF5_24") (pintype "passive"))
      (node (ref "U3") (pin "30") (pinfunction "A5_30") (pintype "passive"))
    )
    (net (code "43") (name "/FMC_A6") (class "Default")
      (node (ref "U1") (pin "71") (pinfunction "PF12_71") (pintype "passive"))
      (node (ref "U3") (pin "31") (pinfunction "A6_31") (pintype "passive"))
    )
    (net (code "44") (name "/FMC_A7") (class "Default")
      (node (ref "U1") (pin "74") (pinfunction "PF13_74") (pintype "passive"))
      (node (ref "U3") (pin "32") (pinfunction "A7_32") (pintype "passive"))
    )
    (net (code "45") (name "/FMC_A8") (class "Default")
      (node (ref "U1") (pin "75") (pinfunction "PF14_75") (pintype "passive"))
      (node (ref "U3") (pin "33") (pinfunction "A8_33") (pintype "passive"))
    )
    (net (code "46") (name "/FMC_A9") (class "Default")
      (node (ref "U1") (pin "76") (pinfunction "PF15_76") (pintype "passive"))
      (node (ref "U3") (pin "34") (pinfunction "A9_34") (pintype "passive"))
    )
    (net (code "47") (name "/FMC_A10") (class "Default")
      (node (ref "U1") (pin "77") (pinfunction "PG0_77") (pintype "passive"))
      (node (ref "U3") (pin "22") (pinfunction "A10/AP_22") (pintype "passive"))
    )
    (net (code "48") (name "/FMC_A11") (class "Default")
      (node (ref "U1") (pin "78") (pinfunction "PG1_78") (pintype "passive"))
      (node (ref "U3") (pin "35") (pinfunction "A11_35") (pintype "passive"))
    )
    (net (code "49") (name "/FMC_BA0") (class "Default")
      (node (ref "U1") (pin "131") (pinfunction "PG4_131") (pintype "passive"))
      (node (ref "U3") (pin "20") (pinfunction "BS0_20") (pintype "passive"))
    )
    (net (code "50") (name "/FMC_BA1") (class "Default")
      (node (ref "U1") (pin "132") (pinfunction "PG5_132") (pintype "passive"))
      (node (ref "U3") (pin "21") (pinfunction "BS1_21") (pintype "passive"))
    )
    (net (code "51") (name "/FMC_D0") (class "Default")
      (node (ref "U1") (pin "116") (pinfunction "PD14_116") (pintype "passive"))
      (node (ref "U3") (pin "2") (pinfunction "DQ0_2") (pintype "passive"))
    )
    (net (code "52") (name "/FMC_D1") (class "Default")
      (node (ref "U1") (pin "117") (pinfunction "PD15_117") (pintype "passive"))
      (node (ref "U3") (pin "4") (pinfunction "DQ1_4") (pintype "passive"))
    )
    (net (code "53") (name "/FMC_D2") (class "Default")
      (node (ref "U1") (pin "164") (pinfunction "PD0_164") (pintype "passive"))
      (node (ref "U3") (pin "5") (pinfunction "DQ2_5") (pintype "passive"))
    )
    (net (code "54") (name "/FMC_D3") (class "Default")
      (node (ref "U1") (pin "165") (pinfunction "PD1_165") (pintype "passive"))
      (node (ref "U3") (pin "7") (pinfunction "DQ3_7") (pintype "passive"))
    )
    (net (code "55") (name "/FMC_D4") (class "Default")
      (node (ref "U1") (pin "79") (pinfunction "PE7_79") (pintype "passive"))
      (node (ref "U3") (pin "8") (pinfunction "DQ4_8") (pintype "passive"))
    )
    (net (code "56") (name "/FMC_D5") (class "Default")
      (node (ref "U1") (pin "80") (pinfunction "PE8_80") (pintype "passive"))
      (node (ref "U3") (pin "10") (pinfunction "DQ5_10") (pintype "passive"))
    )
    (net (code "57") (name "/FMC_D6") (class "Default")
      (node (ref "U1") (pin "81") (pinfunction "PE9_81") (pintype "passive"))
      (node (ref "U3") (pin "11") (pinfunction "DQ6_11") (pintype "passive"))
    )
    (net (code "58") (name "/FMC_D7") (class "Default")
      (node (ref "U1") (pin "84") (pinfunction "PE10_84") (pintype "passive"))
      (node (ref "U3") (pin "13") (pinfunction "DQ7_13") (pintype "passive"))
    )
    (net (code "59") (name "/FMC_D8") (class "Default")
      (node (ref "U1") (pin "85") (pinfunction "PE11_85") (pintype "passive"))
      (node (ref "U3") (pin "42") (pinfunction "DQ8_42") (pintype "passive"))
    )
    (net (code "60") (name "/FMC_D9") (class "Default")
      (node (ref "U1") (pin "86") (pinfunction "PE12_86") (pintype "passive"))
      (node (ref "U3") (pin "44") (pinfunction "DQ9_44") (pintype "passive"))
    )
    (net (code "61") (name "/FMC_D10") (class "Default")
      (node (ref "U1") (pin "87") (pinfunction "PE13_87") (pintype "passive"))
      (node (ref "U3") (pin "45") (pinfunction "DQ10_45") (pintype "passive"))
    )
    (net (code "62") (name "/FMC_D11") (class "Default")
      (node (ref "U1") (pin "88") (pinfunction "PE14_88") (pintype "passive"))
      (node (ref "U3") (pin "47") (pinfunction "DQ11_47") (pintype "passive"))
    )
    (net (code "63") (name "/FMC_D12") (class "Default")
      (node (ref "U1") (pin "89") (pinfunction "PE15_89") (pintype "passive"))
      (node (ref "U3") (pin "48") (pinfunction "DQ12_48") (pintype "passive"))
    )
    (net (code "64") (name "/FMC_D13") (class "Default")
      (node (ref "U1") (pin "108") (pinfunction "PD8_108") (pintype "passive"))
      (node (ref "U3") (pin "50") (pinfunction "DQ13_50") (pintype "passive"))
    )
    (net (code "65") (name "/FMC_D14") (class "Default")
      (node (ref "U1") (pin "109") (pinfunction "PD9_109") (pintype "passive"))
      (node (ref "U3") (pin "51") (pinfunction "DQ14_51") (pintype "passive"))
    )
    (net (code "66") (name "/FMC_D15") (class "Default")
      (node (ref "U1") (pin "110") (pinfunction "PD10_110") (pintype "passive"))
      (node (ref "U3") (pin "53") (pinfunction "DQ15_53") (pintype "passive"))
    )
    (net (code "67") (name "/FMC_NBL0") (class "Default")
      (node (ref "U1") (pin "200") (pinfunction "PE0_200") (pintype "passive"))
      (node (ref "U3") (pin "15") (pinfunction "LDQM_15") (pintype "passive"))
    )
    (net (code "68") (name "/FMC_NBL1") (class "Default")
      (node (ref "U1") (pin "201") (pinfunction "PE1_201") (pintype "passive"))
      (node (ref "U3") (pin "39") (pinfunction "UDQM_39") (pintype "passive"))
    )
    (net (code "69") (name "/FMC_SDCKE0") (class "Default")
      (node (ref "U1") (pin "46") (pinfunction "PH2_46") (pintype "passive"))
      (node (ref "U3") (pin "37") (pinfunction "CKE_37") (pintype "passive"))
    )
    (net (code "70") (name "/FMC_SDCLK") (class "Default")
      (node (ref "U1") (pin "135") (pinfunction "PG8_135") (pintype "passive"))
      (node (ref "U3") (pin "38") (pinfunction "CLK_38") (pintype "passive"))
    )
    (net (code "71") (name "/FMC_SDNCAS") (class "Default")
      (node (ref "U1") (pin "191") (pinfunction "PG15_191") (pintype "passive"))
      (node (ref "U3") (pin "17") (pinfunction "CAS#_17") (pintype "passive"))
    )
    (net (code "72") (name "/FMC_SDNE0") (class "Default")
      (node (ref "U1") (pin "47") (pinfunction "PH3_47") (pintype "passive"))
      (node (ref "U3") (pin "19") (pinfunction "CS#_19") (pintype "passive"))
    )
    (net (code "73") (name "/FMC_SDNRAS") (class "Default")
      (node (ref "U1") (pin "70") (pinfunction "PF11_70") (pintype "passive"))
      (node (ref "U3") (pin "18") (pinfunction "RAS#_18") (pintype "passive"))
    )
    (net (code "74") (name "/FMC_SDNWE") (class "Default")
      (node (ref "U1") (pin "35") (pinfunction "PC0_35") (pintype "passive"))
      (node (ref "U3") (pin "16") (pinfunction "WE#_16") (pintype "passive"))
    )
    (net (code "75") (name "/G0") (class "Default")
      (node (ref "J5") (pin "20") (pinfunction "20_20") (pintype "passive"))
      (node (ref "U1") (pin "119") (pinfunction "PJ7_119") (pintype "passive"))
    )
    (net (code "76") (name "/G1") (class "Default")
      (node (ref "J5") (pin "21") (pinfunction "21_21") (pintype "passive"))
      (node (ref "U1") (pin "120") (pinfunction "PJ8_120") (pintype "passive"))
    )
    (net (code "77") (name "/G2") (class "Default")
      (node (ref "J5") (pin "22") (pinfunction "22_22") (pintype "passive"))
      (node (ref "U1") (pin "121") (pinfunction "PJ9_121") (pintype "passive"))
    )
    (net (code "78") (name "/G3") (class "Default")
      (node (ref "J5") (pin "23") (pinfunction "23_23") (pintype "passive"))
      (node (ref "U1") (pin "122") (pinfunction "PJ10_122") (pintype "passive"))
    )
    (net (code "79") (name "/G4") (class "Default")
      (node (ref "J5") (pin "24") (pinfunction "24_24") (pintype "passive"))
      (node (ref "U1") (pin "123") (pinfunction "PJ11_123") (pintype "passive"))
    )
    (net (code "80") (name "/G5") (class "Default")
      (node (ref "J5") (pin "25") (pinfunction "25_25") (pintype "passive"))
      (node (ref "U1") (pin "126") (pinfunction "PK0_126") (pintype "passive"))
    )
    (net (code "81") (name "/G6") (class "Default")
      (node (ref "J5") (pin "26") (pinfunction "26_26") (pintype "passive"))
      (node (ref "U1") (pin "127") (pinfunction "PK1_127") (pintype "passive"))
    )
    (net (code "82") (name "/G7") (class "Default")
      (node (ref "J5") (pin "27") (pinfunction "27_27") (pintype "passive"))
      (node (ref "U1") (pin "128") (pinfunction "PK2_128") (pintype "passive"))
    )
    (net (code "83") (name "/HS") (class "Default")
      (node (ref "J5") (pin "36") (pinfunction "36_36") (pintype "passive"))
      (node (ref "U1") (pin "19") (pinfunction "PI12_19") (pintype "passive"))
    )
    (net (code "84") (name "/I2C1_SCL") (class "Default")
      (node (ref "J6") (pin "6") (pinfunction "6_6") (pintype "passive"))
      (node (ref "R30") (pin "2") (pinfunction "2_2") (pintype "passive"))
      (node (ref "U1") (pin "195") (pinfunction "PB6_195") (pintype "passive"))
    )
    (net (code "85") (name "/I2C1_SDA") (class "Default")
      (node (ref "J6") (pin "5") (pinfunction "5_5") (pintype "passive"))
      (node (ref "R31") (pin "2") (pinfunction "2_2") (pintype "passive"))
      (node (ref "U1") (pin "196") (pinfunction "PB7_196") (pintype "passive"))
    )
    (net (code "86") (name "/I2C2_SCL") (class "Default")
      (node (ref "R1") (pin "2") (pinfunction "2_2") (pintype "passive"))
      (node (ref "U1") (pin "48") (pinfunction "PH4_48") (pintype "passive"))
    )
    (net (code "87") (name "/I2C2_SDA") (class "Default")
      (node (ref "R2") (pin "2") (pinfunction "2_2") (pintype "passive"))
      (node (ref "U1") (pin "49") (pinfunction "PH5_49") (pintype "passive"))
    )
    (net (code "88") (name "/LEDA") (class "Default")
      (node (ref "C12") (pin "2") (pinfunction "2_2") (pintype "passive"))
      (node (ref "C14") (pin "2") (pinfunction "2_2") (pintype "passive"))
      (node (ref "D1") (pin "2") (pinfunction "K_2") (pintype "passive"))
      (node (ref "J5") (pin "3") (pinfunction "3_3") (pintype "passive"))
      (node (ref "J5") (pin "4") (pinfunction "4_4") (pintype "passive"))
    )
    (net (code "89") (name "/LEDK") (class "Default")
      (node (ref "C12") (pin "1") (pinfunction "1_1") (pintype "passive"))
      (node (ref "J5") (pin "1") (pinfunction "1_1") (pintype "passive"))
      (node (ref "J5") (pin "2") (pinfunction "2_2") (pintype "passive"))
      (node (ref "R10") (pin "1") (pinfunction "1_1") (pintype "passive"))
      (node (ref "U2") (pin "3") (pinfunction "FB_3") (pintype "passive"))
    )
    (net (code "90") (name "/PCLK") (class "Default")
      (node (ref "J5") (pin "38") (pinfunction "38_38") (pintype "passive"))
      (node (ref "U1") (pin "21") (pinfunction "PI14_21") (pintype "passive"))
    )
    (net (code "91") (name "/R0") (class "Default")
      (node (ref "J5") (pin "28") (pinfunction "28_28") (pintype "passive"))
      (node (ref "U1") (pin "64") (pinfunction "PI15_64") (pintype "passive"))
    )
    (net (code "92") (name "/R1") (class "Default")
      (node (ref "J5") (pin "29") (pinfunction "29_29") (pintype "passive"))
      (node (ref "U1") (pin "65") (pinfunction "PJ0_65") (pintype "passive"))
    )
    (net (code "93") (name "/R2") (class "Default")
      (node (ref "J5") (pin "30") (pinfunction "30_30") (pintype "passive"))
      (node (ref "U1") (pin "66") (pinfunction "PJ1_66") (pintype "passive"))
    )
    (net (code "94") (name "/R3") (class "Default")
      (node (ref "J5") (pin "31") (pinfunction "31_31") (pintype "passive"))
      (node (ref "U1") (pin "67") (pinfunction "PJ2_67") (pintype "passive"))
    )
    (net (code "95") (name "/R4") (class "Default")
      (node (ref "J5") (pin "32") (pinfunction "32_32") (pintype "passive"))
      (node (ref "U1") (pin "68") (pinfunction "PJ3_68") (pintype "passive"))
    )
    (net (code "96") (name "/R5") (class "Default")
      (node (ref "J5") (pin "33") (pinfunction "33_33") (pintype "passive"))
      (node (ref "U1") (pin "69") (pinfunction "PJ4_69") (pintype "passive"))
    )
    (net (code "97") (name "/R6") (class "Default")
      (node (ref "J5") (pin "34") (pinfunction "34_34") (pintype "passive"))
      (node (ref "U1") (pin "95") (pinfunction "PJ5_95") (pintype "passive"))
    )
    (net (code "98") (name "/R7") (class "Default")
      (node (ref "J5") (pin "35") (pinfunction "35_35") (pintype "passive"))
      (node (ref "U1") (pin "118") (pinfunction "PJ6_118") (pintype "passive"))
    )
    (net (code "99") (name "/SDIO_CLK") (class "Default")
      (node (ref "J3") (pin "5") (pinfunction "CLK(SCLK)_5") (pintype "passive"))
      (node (ref "R23") (pin "1") (pinfunction "1_1") (pintype "passive"))
      (node (ref "U1") (pin "163") (pinfunction "PC12_163") (pintype "passive"))
    )
    (net (code "100") (name "/SDIO_CMD") (class "Default")
      (node (ref "J3") (pin "3") (pinfunction "CMD(DI)_3") (pintype "passive"))
      (node (ref "R24") (pin "1") (pinfunction "1_1") (pintype "passive"))
      (node (ref "U1") (pin "166") (pinfunction "PD2_166") (pintype "passive"))
    )
    (net (code "101") (name "/SDIO_D0") (class "Default")
      (node (ref "J3") (pin "7") (pinfunction "DAT0(D0)_7") (pintype "passive"))
      (node (ref "R28") (pin "1") (pinfunction "1_1") (pintype "passive"))
      (node (ref "U1") (pin "140") (pinfunction "PC8_140") (pintype "passive"))
    )
    (net (code "102") (name "/SPI1_CLK") (class "Default")
      (node (ref "TP13") (pin "1") (pinfunction "1_1") (pintype "passive"))
      (node (ref "U1") (pin "192") (pinfunction "PB3_192") (pintype "passive"))
    )
    (net (code "103") (name "/SPI1_MISO") (class "Default")
      (node (ref "TP14") (pin "1") (pinfunction "1_1") (pintype "passive"))
      (node (ref "U1") (pin "193") (pinfunction "PB4_193") (pintype "passive"))
    )
    (net (code "104") (name "/SPI1_MOSI") (class "Default")
      (node (ref "TP15") (pin "1") (pinfunction "1_1") (pintype "passive"))
      (node (ref "U1") (pin "194") (pinfunction "PB5_194") (pintype "passive"))
    )
    (net (code "105") (name "/SPI2_CLK") (class "Default")
      (node (ref "J5") (pin "10") (pinfunction "10_10") (pintype "passive"))
      (node (ref "U1") (pin "155") (pinfunction "PI1_155") (pintype "passive"))
    )
    (net (code "106") (name "/SPI2_MISO") (class "Default")
      (node (ref "J5") (pin "7") (pinfunction "7_7") (pintype "passive"))
      (node (ref "U1") (pin "156") (pinfunction "PI2_156") (pintype "passive"))
    )
    (net (code "107") (name "/SPI2_MOSI") (class "Default")
      (node (ref "J5") (pin "11") (pinfunction "11_11") (pintype "passive"))
      (node (ref "U1") (pin "157") (pinfunction "PI3_157") (pintype "passive"))
    )
    (net (code "108") (name "/SPI3_CLK") (class "Default")
      (node (ref "TP24") (pin "1") (pinfunction "1_1") (pintype "passive"))
      (node (ref "U1") (pin "161") (pinfunction "PC10_161") (pintype "passive"))
    )
    (net (code "109") (name "/SPI3_MISO") (class "Default")
      (node (ref "TP25") (pin "1") (pinfunction "1_1") (pintype "passive"))
      (node (ref "U1") (pin "162") (pinfunction "PC11_162") (pintype "passive"))
    )
    (net (code "110") (name "/SPI3_MOSI") (class "Default")
      (node (ref "TP30") (pin "1") (pinfunction "1_1") (pintype "passive"))
      (node (ref "U1") (pin "172") (pinfunction "PD6_172") (pintype "passive"))
    )
    (net (code "111") (name "/SPI4_CLK") (class "Default")
      (node (ref "TP35") (pin "1") (pinfunction "1_1") (pintype "passive"))
      (node (ref "U1") (pin "1") (pinfunction "PE2_1") (pintype "passive"))
    )
    (net (code "112") (name "/SPI4_MISO") (class "Default")
      (node (ref "TP38") (pin "1") (pinfunction "1_1") (pintype "passive"))
      (node (ref "U1") (pin "4") (pinfunction "PE5_4") (pintype "passive"))
    )
    (net (code "113") (name "/SPI4_MOSI") (class "Default")
      (node (ref "TP39") (pin "1") (pinfunction "1_1") (pintype "passive"))
      (node (ref "U1") (pin "5") (pinfunction "PE6_5") (pintype "passive"))
    )
    (net (code "114") (name "/SWCLK") (class "Default")
      (node (ref "J4") (pin "1") (pinfunction "1_1") (pintype "passive"))
      (node (ref "U1") (pin "159") (pinfunction "PA14_159") (pintype "passive"))
    )
    (net (code "115") (name "/SWDIO") (class "Default")
      (node (ref "J4") (pin "2") (pinfunction "2_2") (pintype "passive"))
      (node (ref "U1") (pin "147") (pinfunction "PA13_147") (pintype "passive"))
    )
    (net (code "116") (name "/TIM1_1") (class "Default")
      (node (ref "TP5") (pin "1") (pinfunction "1_1") (pintype "passive"))
      (node (ref "U1") (pin "142") (pinfunction "PA8_142") (pintype "passive"))
    )
    (net (code "117") (name "/TIM1_1N") (class "Default")
      (node (ref "TP18") (pin "1") (pinfunction "1_1") (pintype "passive"))
      (node (ref "U1") (pin "105") (pinfunction "PB13_105") (pintype "passive"))
    )
    (net (code "118") (name "/TIM1_2") (class "Default")
      (node (ref "TP6") (pin "1") (pinfunction "1_1") (pintype "passive"))
      (node (ref "U1") (pin "143") (pinfunction "PA9_143") (pintype "passive"))
    )
    (net (code "119") (name "/TIM1_2N") (class "Default")
      (node (ref "TP10") (pin "1") (pinfunction "1_1") (pintype "passive"))
      (node (ref "U1") (pin "61") (pinfunction "PB0_61") (pintype "passive"))
    )
    (net (code "120") (name "/TIM1_3") (class "Default")
      (node (ref "TP7") (pin "1") (pinfunction "1_1") (pintype "passive"))
      (node (ref "U1") (pin "144") (pinfunction "PA10_144") (pintype "passive"))
    )
    (net (code "121") (name "/TIM1_3N") (class "Default")
      (node (ref "TP11") (pin "1") (pinfunction "1_1") (pintype "passive"))
      (node (ref "U1") (pin "62") (pinfunction "PB1_62") (pintype "passive"))
    )
    (net (code "122") (name "/TIM1_4") (class "Default")
      (node (ref "TP8") (pin "1") (pinfunction "1_1") (pintype "passive"))
      (node (ref "U1") (pin "145") (pinfunction "PA11_145") (pintype "passive"))
    )
    (net (code "123") (name "/TOUCH_INT") (class "Default")
      (node (ref "J6") (pin "2") (pinfunction "2_2") (pintype "passive"))
      (node (ref "U1") (pin "199") (pinfunction "PB9_199") (pintype "passive"))
    )
    (net (code "124") (name "/TOUCH_RST") (class "Default")
      (node (ref "J6") (pin "3") (pinfunction "3_3") (pintype "passive"))
      (node (ref "U1") (pin "198") (pinfunction "PB8_198") (pintype "passive"))
    )
    (net (code "125") (name "/UART3_RX") (class "Default")
      (node (ref "TP17") (pin "1") (pinfunction "1_1") (pintype "passive"))
      (node (ref "U1") (pin "91") (pinfunction "PB11_91") (pintype "passive"))
    )
    (net (code "126") (name "/UART3_TX") (class "Default")
      (node (ref "TP16") (pin "1") (pinfunction "1_1") (pintype "passive"))
      (node (ref "U1") (pin "90") (pinfunction "PB10_90") (pintype "passive"))
    )
    (net (code "127") (name "/UART6_RX") (class "Default")
      (node (ref "TP22") (pin "1") (pinfunction "1_1") (pintype "passive"))
      (node (ref "U1") (pin "139") (pinfunction "PC7_139") (pintype "passive"))
    )
    (net (code "128") (name "/UART6_TX") (class "Default")
      (node (ref "TP21") (pin "1") (pinfunction "1_1") (pintype "passive"))
      (node (ref "U1") (pin "138") (pinfunction "PC6_138") (pintype "passive"))
    )
    (net (code "129") (name "/VS") (class "Default")
      (node (ref "J5") (pin "37") (pinfunction "37_37") (pintype "passive"))
      (node (ref "U1") (pin "20") (pinfunction "PI13_20") (pintype "passive"))
    )
    (net (code "130") (name "3V3") (class "Default")
      (node (ref "C1") (pin "2") (pinfunction "2_2") (pintype "passive"))
      (node (ref "C13") (pin "2") (pinfunction "2_2") (pintype "passive"))
      (node (ref "C17") (pin "2") (pinfunction "2_2") (pintype "passive"))
      (node (ref "C2") (pin "2") (pinfunction "2_2") (pintype "passive"))
      (node (ref "C22") (pin "2") (pinfunction "2_2") (pintype "passive"))
      (node (ref "C3") (pin "2") (pinfunction "2_2") (pintype "passive"))
      (node (ref "C30") (pin "2") (pinfunction "2_2") (pintype "passive"))
      (node (ref "C31") (pin "2") (pinfunction "2_2") (pintype "passive"))
      (node (ref "C33") (pin "2") (pinfunction "2_2") (pintype "passive"))
      (node (ref "C35") (pin "2") (pinfunction "2_2") (pintype "passive"))
      (node (ref "C36") (pin "2") (pinfunction "2_2") (pintype "passive"))
      (node (ref "C37") (pin "2") (pinfunction "2_2") (pintype "passive"))
      (node (ref "C38") (pin "2") (pinfunction "2_2") (pintype "passive"))
      (node (ref "C39") (pin "2") (pinfunction "2_2") (pintype "passive"))
      (node (ref "C4") (pin "2") (pinfunction "2_2") (pintype "passive"))
      (node (ref "C40") (pin "2") (pinfunction "2_2") (pintype "passive"))
      (node (ref "C41") (pin "2") (pinfunction "2_2") (pintype "passive"))
      (node (ref "C42") (pin "2") (pinfunction "2_2") (pintype "passive"))
      (node (ref "C43") (pin "2") (pinfunction "2_2") (pintype "passive"))
      (node (ref "C44") (pin "2") (pinfunction "2_2") (pintype "passive"))
      (node (ref "C46") (pin "2") (pinfunction "2_2") (pintype "passive"))
      (node (ref "C48") (pin "2") (pinfunction "2_2") (pintype "passive"))
      (node (ref "C49") (pin "2") (pinfunction "2_2") (pintype "passive"))
      (node (ref "C5") (pin "2") (pinfunction "2_2") (pintype "passive"))
      (node (ref "C51") (pin "2") (pinfunction "2_2") (pintype "passive"))
      (node (ref "C53") (pin "2") (pinfunction "2_2") (pintype "passive"))
      (node (ref "C54") (pin "2") (pinfunction "2_2") (pintype "passive"))
      (node (ref "C55") (pin "2") (pinfunction "2_2") (pintype "passive"))
      (node (ref "C56") (pin "2") (pinfunction "2_2") (pintype "passive"))
      (node (ref "C57") (pin "2") (pinfunction "2_2") (pintype "passive"))
      (node (ref "C58") (pin "2") (pinfunction "2_2") (pintype "passive"))
      (node (ref "C6") (pin "2") (pinfunction "2_2") (pintype "passive"))
      (node (ref "C8") (pin "2") (pinfunction "2_2") (pintype "passive"))
      (node (ref "J3") (pin "4") (pinfunction "VDD_4") (pintype "passive"))
      (node (ref "J5") (pin "41") (pinfunction "41_41") (pintype "passive"))
      (node (ref "J5") (pin "42") (pinfunction "42_42") (pintype "passive"))
      (node (ref "J6") (pin "4") (pinfunction "4_4") (pintype "passive"))
      (node (ref "L1") (pin "1") (pinfunction "1_1") (pintype "passive"))
      (node (ref "L2") (pin "2") (pinfunction "2_2") (pintype "passive"))
      (node (ref "L3") (pin "2") (pinfunction "2_2") (pintype "passive"))
      (node (ref "L4") (pin "1") (pinfunction "1_1") (pintype "passive"))
      (node (ref "R1") (pin "1") (pinfunction "1_1") (pintype "passive"))
      (node (ref "R19") (pin "1") (pinfunction "1_1") (pintype "passive"))
      (node (ref "R2") (pin "1") (pinfunction "1_1") (pintype "passive"))
      (node (ref "R23") (pin "2") (pinfunction "2_2") (pintype "passive"))
      (node (ref "R24") (pin "2") (pinfunction "2_2") (pintype "passive"))
      (node (ref "R25") (pin "2") (pinfunction "2_2") (pintype "passive"))
      (node (ref "R26") (pin "2") (pinfunction "2_2") (pintype "passive"))
      (node (ref "R27") (pin "2") (pinfunction "2_2") (pintype "passive"))
      (node (ref "R28") (pin "2") (pinfunction "2_2") (pintype "passive"))
      (node (ref "R29") (pin "1") (pinfunction "1_1") (pintype "passive"))
      (node (ref "R30") (pin "1") (pinfunction "1_1") (pintype "passive"))
      (node (ref "R31") (pin "1") (pinfunction "1_1") (pintype "passive"))
      (node (ref "R6") (pin "2") (pinfunction "2_2") (pintype "passive"))
      (node (ref "U1") (pin "103") (pinfunction "VDD_103") (pintype "passive"))
      (node (ref "U1") (pin "115") (pinfunction "VDD_115") (pintype "passive"))
      (node (ref "U1") (pin "124") (pinfunction "VDD_124") (pintype "passive"))
      (node (ref "U1") (pin "137") (pinfunction "VDD_137") (pintype "passive"))
      (node (ref "U1") (pin "15") (pinfunction "VDD_15") (pintype "passive"))
      (node (ref "U1") (pin "150") (pinfunction "VDD_150") (pintype "passive"))
      (node (ref "U1") (pin "158") (pinfunction "VDD_158") (pintype "passive"))
      (node (ref "U1") (pin "171") (pinfunction "VDD_171") (pintype "passive"))
      (node (ref "U1") (pin "185") (pinfunction "VDD_185") (pintype "passive"))
      (node (ref "U1") (pin "203") (pinfunction "PDR_ON_203") (pintype "passive"))
      (node (ref "U1") (pin "204") (pinfunction "VDD_204") (pintype "passive"))
      (node (ref "U1") (pin "26") (pinfunction "VDD_26") (pintype "passive"))
      (node (ref "U1") (pin "39") (pinfunction "VDD_39") (pintype "passive"))
      (node (ref "U1") (pin "52") (pinfunction "VDD_52") (pintype "passive"))
      (node (ref "U1") (pin "59") (pinfunction "VDD_59") (pintype "passive"))
      (node (ref "U1") (pin "6") (pinfunction "VBAT_6") (pintype "passive"))
      (node (ref "U1") (pin "73") (pinfunction "VDD_73") (pintype "passive"))
      (node (ref "U1") (pin "83") (pinfunction "VDD_83") (pintype "passive"))
      (node (ref "U1") (pin "94") (pinfunction "VDD_94") (pintype "passive"))
      (node (ref "U2") (pin "5") (pinfunction "VIN_5") (pintype "passive"))
      (node (ref "U3") (pin "1") (pinfunction "VDD_1") (pintype "passive"))
      (node (ref "U3") (pin "14") (pinfunction "VDD_14") (pintype "passive"))
      (node (ref "U3") (pin "27") (pinfunction "VDD_27") (pintype "passive"))
      (node (ref "U3") (pin "3") (pinfunction "VDDQ_3") (pintype "passive"))
      (node (ref "U3") (pin "43") (pinfunction "VDDQ_43") (pintype "passive"))
      (node (ref "U3") (pin "49") (pinfunction "VDDQ_49") (pintype "passive"))
      (node (ref "U3") (pin "9") (pinfunction "VDDQ_9") (pintype "passive"))
      (node (ref "U4") (pin "9") (pinfunction "VDDIO_9") (pintype "passive"))
      (node (ref "U7") (pin "5") (pinfunction "Vio_5") (pintype "passive"))
    )
    (net (code "131") (name "3V3_REF") (class "Default")
      (node (ref "C27") (pin "2") (pinfunction "2_2") (pintype "passive"))
      (node (ref "C34") (pin "2") (pinfunction "2_2") (pintype "passive"))
      (node (ref "U1") (pin "41") (pinfunction "VREF+_41") (pintype "passive"))
      (node (ref "U5") (pin "2") (pinfunction "OUT_2") (pintype "passive"))
    )
    (net (code "132") (name "5V") (class "Default")
      (node (ref "C18") (pin "2") (pinfunction "2_2") (pintype "passive"))
      (node (ref "C19") (pin "2") (pinfunction "2_2") (pintype "passive"))
      (node (ref "C20") (pin "2") (pinfunction "2_2") (pintype "passive"))
      (node (ref "J1") (pin "1") (pinfunction "VBUS_1") (pintype "passive"))
      (node (ref "U5") (pin "1") (pinfunction "IN_1") (pintype "passive"))
      (node (ref "U6") (pin "3") (pinfunction "VIN_3") (pintype "passive"))
      (node (ref "U7") (pin "3") (pinfunction "Vcc_3") (pintype "passive"))
    )
    (net (code "133") (name "AGND") (class "Default")
      (node (ref "C20") (pin "1") (pinfunction "1_1") (pintype "passive"))
      (node (ref "C27") (pin "1") (pinfunction "1_1") (pintype "passive"))
      (node (ref "C34") (pin "1") (pinfunction "1_1") (pintype "passive"))
      (node (ref "C50") (pin "1") (pinfunction "1_1") (pintype "passive"))
      (node (ref "C52") (pin "1") (pinfunction "1_1") (pintype "passive"))
      (node (ref "L5") (pin "2") (pinfunction "2_2") (pintype "passive"))
      (node (ref "U1") (pin "40") (pinfunction "VSSA_40") (pintype "passive"))
      (node (ref "U5") (pin "3") (pinfunction "GND_3") (pintype "passive"))
    )
    (net (code "134") (name "EARTH") (class "Default")
      (node (ref "J2") (pin "8") (pinfunction "CHS_GND_8") (pintype "passive"))
      (node (ref "J2") (pin "SH1") (pinfunction "SH1_SH1") (pintype "passive"))
      (node (ref "J2") (pin "SH2") (pinfunction "SH2_SH2") (pintype "passive"))
      (node (ref "R22") (pin "1") (pinfunction "1_1") (pintype "passive"))
    )
    (net (code "135") (name "GND") (class "Default")
      (node (ref "C1") (pin "1") (pinfunction "1_1") (pintype "passive"))
      (node (ref "C10") (pin "1") (pinfunction "1_1") (pintype "passive"))
      (node (ref "C11") (pin "1") (pinfunction "1_1") (pintype "passive"))
      (node (ref "C13") (pin "1") (pinfunction "1_1") (pintype "passive"))
      (node (ref "C14") (pin "1") (pinfunction "1_1") (pintype "passive"))
      (node (ref "C15") (pin "1") (pinfunction "1_1") (pintype "passive"))
      (node (ref "C16") (pin "1") (pinfunction "1_1") (pintype "passive"))
      (node (ref "C17") (pin "1") (pinfunction "1_1") (pintype "passive"))
      (node (ref "C18") (pin "1") (pinfunction "1_1") (pintype "passive"))
      (node (ref "C19") (pin "1") (pinfunction "1_1") (pintype "passive"))
      (node (ref "C2") (pin "1") (pinfunction "1_1") (pintype "passive"))
      (node (ref "C21") (pin "1") (pinfunction "1_1") (pintype "passive"))
      (node (ref "C22") (pin "1") (pinfunction "1_1") (pintype "passive"))
      (node (ref "C23") (pin "1") (pinfunction "1_1") (pintype "passive"))
      (node (ref "C24") (pin "1") (pinfunction "1_1") (pintype "passive"))
      (node (ref "C25") (pin "1") (pinfunction "1_1") (pintype "passive"))
      (node (ref "C26") (pin "1") (pinfunction "1_1") (pintype "passive"))
      (node (ref "C3") (pin "1") (pinfunction "1_1") (pintype "passive"))
      (node (ref "C30") (pin "1") (pinfunction "1_1") (pintype "passive"))
      (node (ref "C31") (pin "1") (pinfunction "1_1") (pintype "passive"))
      (node (ref "C32") (pin "1") (pinfunction "1_1") (pintype "passive"))
      (node (ref "C33") (pin "1") (pinfunction "1_1") (pintype "passive"))
      (node (ref "C35") (pin "1") (pinfunction "1_1") (pintype "passive"))
      (node (ref "C36") (pin "1") (pinfunction "1_1") (pintype "passive"))
      (node (ref "C37") (pin "1") (pinfunction "1_1") (pintype "passive"))
      (node (ref "C38") (pin "1") (pinfunction "1_1") (pintype "passive"))
      (node (ref "C39") (pin "1") (pinfunction "1_1") (pintype "passive"))
      (node (ref "C4") (pin "1") (pinfunction "1_1") (pintype "passive"))
      (node (ref "C40") (pin "1") (pinfunction "1_1") (pintype "passive"))
      (node (ref "C41") (pin "1") (pinfunction "1_1") (pintype "passive"))
      (node (ref "C42") (pin "1") (pinfunction "1_1") (pintype "passive"))
      (node (ref "C43") (pin "1") (pinfunction "1_1") (pintype "passive"))
      (node (ref "C44") (pin "1") (pinfunction "1_1") (pintype "passive"))
      (node (ref "C45") (pin "1") (pinfunction "1_1") (pintype "passive"))
      (node (ref "C46") (pin "1") (pinfunction "1_1") (pintype "passive"))
      (node (ref "C47") (pin "1") (pinfunction "1_1") (pintype "passive"))
      (node (ref "C48") (pin "1") (pinfunction "1_1") (pintype "passive"))
      (node (ref "C49") (pin "1") (pinfunction "1_1") (pintype "passive"))
      (node (ref "C5") (pin "1") (pinfunction "1_1") (pintype "passive"))
      (node (ref "C51") (pin "1") (pinfunction "1_1") (pintype "passive"))
      (node (ref "C53") (pin "1") (pinfunction "1_1") (pintype "passive"))
      (node (ref "C54") (pin "1") (pinfunction "1_1") (pintype "passive"))
      (node (ref "C55") (pin "1") (pinfunction "1_1") (pintype "passive"))
      (node (ref "C56") (pin "1") (pinfunction "1_1") (pintype "passive"))
      (node (ref "C57") (pin "1") (pinfunction "1_1") (pintype "passive"))
      (node (ref "C58") (pin "1") (pinfunction "1_1") (pintype "passive"))
      (node (ref "C6") (pin "1") (pinfunction "1_1") (pintype "passive"))
      (node (ref "C7") (pin "1") (pinfunction "1_1") (pintype "passive"))
      (node (ref "C8") (pin "1") (pinfunction "1_1") (pintype "passive"))
      (node (ref "C9") (pin "1") (pinfunction "1_1") (pintype "passive"))
      (node (ref "J1") (pin "4") (pinfunction "ID_4") (pintype "passive"))
      (node (ref "J1") (pin "5") (pinfunction "GND_5") (pintype "passive"))
      (node (ref "J1") (pin "6") (pinfunction "SH1_6") (pintype "passive"))
      (node (ref "J1") (pin "7") (pinfunction "SH2_7") (pintype "passive"))
      (node (ref "J1") (pin "8") (pinfunction "SH3_8") (pintype "passive"))
      (node (ref "J1") (pin "9") (pinfunction "SH4_9") (pintype "passive"))
      (node (ref "J3") (pin "10") (pinfunction "GND_10") (pintype "passive"))
      (node (ref "J3") (pin "11") (pinfunction "GND_11") (pintype "passive"))
      (node (ref "J3") (pin "12") (pinfunction "GND_12") (pintype "passive"))
      (node (ref "J3") (pin "13") (pinfunction "GND_13") (pintype "passive"))
      (node (ref "J3") (pin "6") (pinfunction "VSS_6") (pintype "passive"))
      (node (ref "J4") (pin "3") (pinfunction "3_3") (pintype "passive"))
      (node (ref "J5") (pin "53") (pinfunction "53_53") (pintype "passive"))
      (node (ref "J5") (pin "54") (pinfunction "54_54") (pintype "passive"))
      (node (ref "J6") (pin "1") (pinfunction "1_1") (pintype "passive"))
      (node (ref "L5") (pin "1") (pinfunction "1_1") (pintype "passive"))
      (node (ref "R10") (pin "2") (pinfunction "2_2") (pintype "passive"))
      (node (ref "R13") (pin "1") (pinfunction "1_1") (pintype "passive"))
      (node (ref "R16") (pin "1") (pinfunction "1_1") (pintype "passive"))
      (node (ref "R17") (pin "1") (pinfunction "1_1") (pintype "passive"))
      (node (ref "R18") (pin "1") (pinfunction "1_1") (pintype "passive"))
      (node (ref "R21") (pin "2") (pinfunction "2_2") (pintype "passive"))
      (node (ref "R22") (pin "2") (pinfunction "2_2") (pintype "passive"))
      (node (ref "R3") (pin "1") (pinfunction "1_1") (pintype "passive"))
      (node (ref "R4") (pin "1") (pinfunction "1_1") (pintype "passive"))
      (node (ref "R5") (pin "2") (pinfunction "2_2") (pintype "passive"))
      (node (ref "R7") (pin "1") (pinfunction "1_1") (pintype "passive"))
      (node (ref "U1") (pin "114") (pinfunction "VSS_114") (pintype "passive"))
      (node (ref "U1") (pin "125") (pinfunction "VSS_125") (pintype "passive"))
      (node (ref "U1") (pin "136") (pinfunction "VSS_136") (pintype "passive"))
      (node (ref "U1") (pin "14") (pinfunction "VSS_14") (pintype "passive"))
      (node (ref "U1") (pin "149") (pinfunction "VSS_149") (pintype "passive"))
      (node (ref "U1") (pin "170") (pinfunction "VSS_170") (pintype "passive"))
      (node (ref "U1") (pin "184") (pinfunction "VSS_184") (pintype "passive"))
      (node (ref "U1") (pin "197") (pinfunction "BOOT0_197") (pintype "passive"))
      (node (ref "U1") (pin "202") (pinfunction "VSS_202") (pintype "passive"))
      (node (ref "U1") (pin "25") (pinfunction "VSS_25") (pintype "passive"))
      (node (ref "U1") (pin "51") (pinfunction "VSS_51") (pintype "passive"))
      (node (ref "U1") (pin "60") (pinfunction "VSS_60") (pintype "passive"))
      (node (ref "U1") (pin "72") (pinfunction "VSS_72") (pintype "passive"))
      (node (ref "U1") (pin "82") (pinfunction "VSS_82") (pintype "passive"))
      (node (ref "U1") (pin "93") (pinfunction "VSS_93") (pintype "passive"))
      (node (ref "U2") (pin "2") (pinfunction "GND_2") (pintype "passive"))
      (node (ref "U3") (pin "12") (pinfunction "VSSQ_12") (pintype "passive"))
      (node (ref "U3") (pin "28") (pinfunction "VSS_28") (pintype "passive"))
      (node (ref "U3") (pin "41") (pinfunction "VSS_41") (pintype "passive"))
      (node (ref "U3") (pin "46") (pinfunction "VSSQ_46") (pintype "passive"))
      (node (ref "U3") (pin "52") (pinfunction "VSSQ_52") (pintype "passive"))
      (node (ref "U3") (pin "54") (pinfunction "VSS_54") (pintype "passive"))
      (node (ref "U3") (pin "6") (pinfunction "VSSQ_6") (pintype "passive"))
      (node (ref "U4") (pin "25") (pinfunction "EP_25") (pintype "passive"))
      (node (ref "U6") (pin "1") (pinfunction "GND_1") (pintype "passive"))
      (node (ref "U7") (pin "2") (pinfunction "GND_2") (pintype "passive"))
      (node (ref "U7") (pin "8") (pinfunction "STB_8") (pintype "passive"))
      (node (ref "U7") (pin "9") (pinfunction "EP_9") (pintype "passive"))
      (node (ref "X1") (pin "2") (pinfunction "2_2") (pintype "passive"))
      (node (ref "X1") (pin "3") (pinfunction "3_3") (pintype "passive"))
      (node (ref "X2") (pin "2") (pinfunction "GND_2") (pintype "passive"))
      (node (ref "X2") (pin "4") (pinfunction "GND_4") (pintype "passive"))
      (node (ref "X3") (pin "2") (pinfunction "GND_2") (pintype "passive"))
      (node (ref "X3") (pin "4") (pinfunction "GND_4") (pintype "passive"))
    )
    (net (code "136") (name "Net-(C29-Pad2)") (class "Default")
      (node (ref "C29") (pin "2") (pinfunction "2_2") (pintype "passive"))
      (node (ref "R19") (pin "2") (pinfunction "2_2") (pintype "passive"))
      (node (ref "R20") (pin "1") (pinfunction "1_1") (pintype "passive"))
    )
    (net (code "137") (name "Net-(D1-A)") (class "Default")
      (node (ref "D1") (pin "1") (pinfunction "A_1") (pintype "passive"))
      (node (ref "L1") (pin "2") (pinfunction "2_2") (pintype "passive"))
      (node (ref "U2") (pin "1") (pinfunction "SW_1") (pintype "passive"))
    )
    (net (code "138") (name "Net-(J1-D+)") (class "Default")
      (node (ref "J1") (pin "3") (pinfunction "D+_3") (pintype "passive"))
      (node (ref "R9") (pin "2") (pinfunction "2_2") (pintype "passive"))
    )
    (net (code "139") (name "Net-(J1-D-)") (class "Default")
      (node (ref "J1") (pin "2") (pinfunction "D-_2") (pintype "passive"))
      (node (ref "R8") (pin "2") (pinfunction "2_2") (pintype "passive"))
    )
    (net (code "140") (name "Net-(J2-Pad10)") (class "Default")
      (node (ref "J2") (pin "10") (pinfunction "10_10") (pintype "passive"))
      (node (ref "R18") (pin "2") (pinfunction "2_2") (pintype "passive"))
    )
    (net (code "141") (name "Net-(J2-Pad11)") (class "Default")
      (node (ref "J2") (pin "11") (pinfunction "11_11") (pintype "passive"))
      (node (ref "R17") (pin "2") (pinfunction "2_2") (pintype "passive"))
    )
    (net (code "142") (name "Net-(J2-RD+)") (class "Default")
      (node (ref "J2") (pin "3") (pinfunction "RD+_3") (pintype "passive"))
      (node (ref "R14") (pin "1") (pinfunction "1_1") (pintype "passive"))
      (node (ref "U4") (pin "23") (pinfunction "RXP_23") (pintype "passive"))
    )
    (net (code "143") (name "Net-(J2-RD-)") (class "Default")
      (node (ref "J2") (pin "6") (pinfunction "RD-_6") (pintype "passive"))
      (node (ref "R15") (pin "1") (pinfunction "1_1") (pintype "passive"))
      (node (ref "U4") (pin "22") (pinfunction "RXN_22") (pintype "passive"))
    )
    (net (code "144") (name "Net-(J2-TD+)") (class "Default")
      (node (ref "J2") (pin "1") (pinfunction "TD+_1") (pintype "passive"))
      (node (ref "R11") (pin "1") (pinfunction "1_1") (pintype "passive"))
      (node (ref "U4") (pin "21") (pinfunction "TXP_21") (pintype "passive"))
    )
    (net (code "145") (name "Net-(J2-TD-)") (class "Default")
      (node (ref "J2") (pin "2") (pinfunction "TD-_2") (pintype "passive"))
      (node (ref "R12") (pin "1") (pinfunction "1_1") (pintype "passive"))
      (node (ref "U4") (pin "20") (pinfunction "TXN_20") (pintype "passive"))
    )
    (net (code "146") (name "Net-(J3-CD)") (class "Default")
      (node (ref "J3") (pin "9") (pinfunction "CD_9") (pintype "passive"))
      (node (ref "TP70") (pin "1") (pinfunction "1_1") (pintype "passive"))
    )
    (net (code "147") (name "Net-(J3-CDDAT3(CS))") (class "Default")
      (node (ref "J3") (pin "2") (pinfunction "CDDAT3(CS)_2") (pintype "passive"))
      (node (ref "R25") (pin "1") (pinfunction "1_1") (pintype "passive"))
    )
    (net (code "148") (name "Net-(J3-DAT1(RSV))") (class "Default")
      (node (ref "J3") (pin "8") (pinfunction "DAT1(RSV)_8") (pintype "passive"))
      (node (ref "R27") (pin "1") (pinfunction "1_1") (pintype "passive"))
    )
    (net (code "149") (name "Net-(J3-DAT2(RSV))") (class "Default")
      (node (ref "J3") (pin "1") (pinfunction "DAT2(RSV)_1") (pintype "passive"))
      (node (ref "R26") (pin "1") (pinfunction "1_1") (pintype "passive"))
    )
    (net (code "150") (name "Net-(U1A-PA3)") (class "Default")
      (node (ref "TP1") (pin "1") (pinfunction "1_1") (pintype "passive"))
      (node (ref "U1") (pin "50") (pinfunction "PA3_50") (pintype "passive"))
    )
    (net (code "151") (name "Net-(U1A-PA15)") (class "Default")
      (node (ref "TP9") (pin "1") (pinfunction "1_1") (pintype "passive"))
      (node (ref "U1") (pin "160") (pinfunction "PA15_160") (pintype "passive"))
    )
    (net (code "152") (name "Net-(U1A-PB2)") (class "Default")
      (node (ref "TP12") (pin "1") (pinfunction "1_1") (pintype "passive"))
      (node (ref "U1") (pin "63") (pinfunction "PB2_63") (pintype "passive"))
    )
    (net (code "153") (name "Net-(U1A-PC2)") (class "Default")
      (node (ref "TP19") (pin "1") (pinfunction "1_1") (pintype "passive"))
      (node (ref "U1") (pin "37") (pinfunction "PC2_37") (pintype "passive"))
    )
    (net (code "154") (name "Net-(U1A-PC3)") (class "Default")
      (node (ref "TP20") (pin "1") (pinfunction "1_1") (pintype "passive"))
      (node (ref "U1") (pin "38") (pinfunction "PC3_38") (pintype "passive"))
    )
    (net (code "155") (name "Net-(U1A-PC9)") (class "Default")
      (node (ref "TP23") (pin "1") (pinfunction "1_1") (pintype "passive"))
      (node (ref "U1") (pin "141") (pinfunction "PC9_141") (pintype "passive"))
    )
    (net (code "156") (name "Net-(U1A-PC13)") (class "Default")
      (node (ref "TP26") (pin "1") (pinfunction "1_1") (pintype "passive"))
      (node (ref "U1") (pin "8") (pinfunction "PC13_8") (pintype "passive"))
    )
    (net (code "157") (name "Net-(U1A-PC14-OSC32_IN)") (class "Default")
      (node (ref "C10") (pin "2") (pinfunction "2_2") (pintype "passive"))
      (node (ref "U1") (pin "9") (pinfunction "PC14-OSC32_IN_9") (pintype "passive"))
      (node (ref "X1") (pin "1") (pinfunction "OSC1_1") (pintype "passive"))
    )
    (net (code "158") (name "Net-(U1A-PC15-OSC32_OUT)") (class "Default")
      (node (ref "C7") (pin "2") (pinfunction "2_2") (pintype "passive"))
      (node (ref "U1") (pin "10") (pinfunction "PC15-OSC32_OUT_10") (pintype "passive"))
      (node (ref "X1") (pin "4") (pinfunction "OSC2_4") (pintype "passive"))
    )
    (net (code "159") (name "Net-(U1A-PD3)") (class "Default")
      (node (ref "TP27") (pin "1") (pinfunction "1_1") (pintype "passive"))
      (node (ref "U1") (pin "167") (pinfunction "PD3_167") (pintype "passive"))
    )
    (net (code "160") (name "Net-(U1A-PD4)") (class "Default")
      (node (ref "TP28") (pin "1") (pinfunction "1_1") (pintype "passive"))
      (node (ref "U1") (pin "168") (pinfunction "PD4_168") (pintype "passive"))
    )
    (net (code "161") (name "Net-(U1A-PD5)") (class "Default")
      (node (ref "TP29") (pin "1") (pinfunction "1_1") (pintype "passive"))
      (node (ref "U1") (pin "169") (pinfunction "PD5_169") (pintype "passive"))
    )
    (net (code "162") (name "Net-(U1A-PD7)") (class "Default")
      (node (ref "TP31") (pin "1") (pinfunction "1_1") (pintype "passive"))
      (node (ref "U1") (pin "173") (pinfunction "PD7_173") (pintype "passive"))
    )
    (net (code "163") (name "Net-(U1A-PD11)") (class "Default")
      (node (ref "TP32") (pin "1") (pinfunction "1_1") (pintype "passive"))
      (node (ref "U1") (pin "111") (pinfunction "PD11_111") (pintype "passive"))
    )
    (net (code "164") (name "Net-(U1A-PD12)") (class "Default")
      (node (ref "TP33") (pin "1") (pinfunction "1_1") (pintype "passive"))
      (node (ref "U1") (pin "112") (pinfunction "PD12_112") (pintype "passive"))
    )
    (net (code "165") (name "Net-(U1A-PD13)") (class "Default")
      (node (ref "TP34") (pin "1") (pinfunction "1_1") (pintype "passive"))
      (node (ref "U1") (pin "113") (pinfunction "PD13_113") (pintype "passive"))
    )
    (net (code "166") (name "Net-(U1B-PE3)") (class "Default")
      (node (ref "TP36") (pin "1") (pinfunction "1_1") (pintype "passive"))
      (node (ref "U1") (pin "2") (pinfunction "PE3_2") (pintype "passive"))
    )
    (net (code "167") (name "Net-(U1B-PE4)") (class "Default")
      (node (ref "TP37") (pin "1") (pinfunction "1_1") (pintype "passive"))
      (node (ref "U1") (pin "3") (pinfunction "PE4_3") (pintype "passive"))
    )
    (net (code "168") (name "Net-(U1B-PG2)") (class "Default")
      (node (ref "TP45") (pin "1") (pinfunction "1_1") (pintype "passive"))
      (node (ref "U1") (pin "129") (pinfunction "PG2_129") (pintype "passive"))
    )
    (net (code "169") (name "Net-(U1B-PG3)") (class "Default")
      (node (ref "TP46") (pin "1") (pinfunction "1_1") (pintype "passive"))
      (node (ref "U1") (pin "130") (pinfunction "PG3_130") (pintype "passive"))
    )
    (net (code "170") (name "Net-(U1B-PG6)") (class "Default")
      (node (ref "TP47") (pin "1") (pinfunction "1_1") (pintype "passive"))
      (node (ref "U1") (pin "133") (pinfunction "PG6_133") (pintype "passive"))
    )
    (net (code "171") (name "Net-(U1B-PG7)") (class "Default")
      (node (ref "TP48") (pin "1") (pinfunction "1_1") (pintype "passive"))
      (node (ref "U1") (pin "134") (pinfunction "PG7_134") (pintype "passive"))
    )
    (net (code "172") (name "Net-(U1B-PG9)") (class "Default")
      (node (ref "TP49") (pin "1") (pinfunction "1_1") (pintype "passive"))
      (node (ref "U1") (pin "178") (pinfunction "PG9_178") (pintype "passive"))
    )
    (net (code "173") (name "Net-(U1B-PG10)") (class "Default")
      (node (ref "TP50") (pin "1") (pinfunction "1_1") (pintype "passive"))
      (node (ref "U1") (pin "179") (pinfunction "PG10_179") (pintype "passive"))
    )
    (net (code "174") (name "Net-(U1B-PG13)") (class "Default")
      (node (ref "TP51") (pin "1") (pinfunction "1_1") (pintype "passive"))
      (node (ref "U1") (pin "182") (pinfunction "PG13_182") (pintype "passive"))
    )
    (net (code "175") (name "Net-(U1B-PH0-OSC_IN)") (class "Default")
      (node (ref "C26") (pin "2") (pinfunction "2_2") (pintype "passive"))
      (node (ref "U1") (pin "32") (pinfunction "PH0-OSC_IN_32") (pintype "passive"))
      (node (ref "X3") (pin "3") (pinfunction "X2_3") (pintype "passive"))
    )
    (net (code "176") (name "Net-(U1B-PH1-OSC_OUT)") (class "Default")
      (node (ref "C25") (pin "2") (pinfunction "2_2") (pintype "passive"))
      (node (ref "U1") (pin "33") (pinfunction "PH1-OSC_OUT_33") (pintype "passive"))
      (node (ref "X3") (pin "1") (pinfunction "X1_1") (pintype "passive"))
    )
    (net (code "177") (name "Net-(U1B-PH6)") (class "Default")
      (node (ref "TP52") (pin "1") (pinfunction "1_1") (pintype "passive"))
      (node (ref "U1") (pin "96") (pinfunction "PH6_96") (pintype "passive"))
    )
    (net (code "178") (name "Net-(U1B-PH7)") (class "Default")
      (node (ref "TP53") (pin "1") (pinfunction "1_1") (pintype "passive"))
      (node (ref "U1") (pin "97") (pinfunction "PH7_97") (pintype "passive"))
    )
    (net (code "179") (name "Net-(U1B-PH8)") (class "Default")
      (node (ref "TP54") (pin "1") (pinfunction "1_1") (pintype "passive"))
      (node (ref "U1") (pin "98") (pinfunction "PH8_98") (pintype "passive"))
    )
    (net (code "180") (name "Net-(U1B-PH9)") (class "Default")
      (node (ref "TP55") (pin "1") (pinfunction "1_1") (pintype "passive"))
      (node (ref "U1") (pin "99") (pinfunction "PH9_99") (pintype "passive"))
    )
    (net (code "181") (name "Net-(U1B-PH10)") (class "Default")
      (node (ref "TP56") (pin "1") (pinfunction "1_1") (pintype "passive"))
      (node (ref "U1") (pin "100") (pinfunction "PH10_100") (pintype "passive"))
    )
    (net (code "182") (name "Net-(U1B-PH11)") (class "Default")
      (node (ref "TP57") (pin "1") (pinfunction "1_1") (pintype "passive"))
      (node (ref "U1") (pin "101") (pinfunction "PH11_101") (pintype "passive"))
    )
    (net (code "183") (name "Net-(U1B-PH12)") (class "Default")
      (node (ref "TP58") (pin "1") (pinfunction "1_1") (pintype "passive"))
      (node (ref "U1") (pin "102") (pinfunction "PH12_102") (pintype "passive"))
    )
    (net (code "184") (name "Net-(U1B-PH13)") (class "Default")
      (node (ref "TP59") (pin "1") (pinfunction "1_1") (pintype "passive"))
      (node (ref "U1") (pin "151") (pinfunction "PH13_151") (pintype "passive"))
    )
    (net (code "185") (name "Net-(U1C-NRST)") (class "Default")
      (node (ref "C32") (pin "2") (pinfunction "2_2") (pintype "passive"))
      (node (ref "R29") (pin "2") (pinfunction "2_2") (pintype "passive"))
      (node (ref "U1") (pin "34") (pinfunction "NRST_34") (pintype "passive"))
    )
    (net (code "186") (name "Net-(U1C-PI4)") (class "Default")
      (node (ref "TP62") (pin "1") (pinfunction "1_1") (pintype "passive"))
      (node (ref "U1") (pin "205") (pinfunction "PI4_205") (pintype "passive"))
    )
    (net (code "187") (name "Net-(U1C-PI5)") (class "Default")
      (node (ref "TP63") (pin "1") (pinfunction "1_1") (pintype "passive"))
      (node (ref "U1") (pin "206") (pinfunction "PI5_206") (pintype "passive"))
    )
    (net (code "188") (name "Net-(U1C-PI6)") (class "Default")
      (node (ref "TP64") (pin "1") (pinfunction "1_1") (pintype "passive"))
      (node (ref "U1") (pin "207") (pinfunction "PI6_207") (pintype "passive"))
    )
    (net (code "189") (name "Net-(U1C-PI7)") (class "Default")
      (node (ref "TP65") (pin "1") (pinfunction "1_1") (pintype "passive"))
      (node (ref "U1") (pin "208") (pinfunction "PI7_208") (pintype "passive"))
    )
    (net (code "190") (name "Net-(U1C-PI8)") (class "Default")
      (node (ref "TP66") (pin "1") (pinfunction "1_1") (pintype "passive"))
      (node (ref "U1") (pin "7") (pinfunction "PI8_7") (pintype "passive"))
    )
    (net (code "191") (name "Net-(U1C-PI10)") (class "Default")
      (node (ref "TP67") (pin "1") (pinfunction "1_1") (pintype "passive"))
      (node (ref "U1") (pin "12") (pinfunction "PI10_12") (pintype "passive"))
    )
    (net (code "192") (name "Net-(U1C-PI11)") (class "Default")
      (node (ref "TP68") (pin "1") (pinfunction "1_1") (pintype "passive"))
      (node (ref "U1") (pin "13") (pinfunction "PI11_13") (pintype "passive"))
    )
    (net (code "193") (name "Net-(U1C-PK3)") (class "Default")
      (node (ref "TP69") (pin "1") (pinfunction "1_1") (pintype "passive"))
      (node (ref "U1") (pin "186") (pinfunction "PK3_186") (pintype "passive"))
    )
    (net (code "194") (name "Net-(U1D-VCAP_1)") (class "Default")
      (node (ref "C47") (pin "2") (pinfunction "2_2") (pintype "passive"))
      (node (ref "U1") (pin "92") (pinfunction "VCAP_1_92") (pintype "passive"))
    )
    (net (code "195") (name "Net-(U1D-VCAP_2)") (class "Default")
      (node (ref "C45") (pin "2") (pinfunction "2_2") (pintype "passive"))
      (node (ref "U1") (pin "148") (pinfunction "VCAP_2_148") (pintype "passive"))
    )
    (net (code "196") (name "Net-(U1D-VDDA)") (class "Default")
      (node (ref "C50") (pin "2") (pinfunction "2_2") (pintype "passive"))
      (node (ref "C52") (pin "2") (pinfunction "2_2") (pintype "passive"))
      (node (ref "L4") (pin "2") (pinfunction "2_2") (pintype "passive"))
      (node (ref "U1") (pin "42") (pinfunction "VDDA_42") (pintype "passive"))
    )
    (net (code "197") (name "Net-(U4-LED1{slash}REGOFF)") (class "Default")
      (node (ref "J2") (pin "9") (pinfunction "9_9") (pintype "passive"))
      (node (ref "U4") (pin "3") (pinfunction "LED1/REGOFF_3") (pintype "passive"))
    )
    (net (code "198") (name "Net-(U4-LED2{slash}nINTSEL)") (class "Default")
      (node (ref "J2") (pin "12") (pinfunction "12_12") (pintype "passive"))
      (node (ref "R16") (pin "2") (pinfunction "2_2") (pintype "passive"))
      (node (ref "U4") (pin "2") (pinfunction "LED2/nINTSEL_2") (pintype "passive"))
    )
    (net (code "199") (name "Net-(U4-RBIAS)") (class "Default")
      (node (ref "R13") (pin "2") (pinfunction "2_2") (pintype "passive"))
      (node (ref "U4") (pin "24") (pinfunction "RBIAS_24") (pintype "passive"))
    )
    (net (code "200") (name "Net-(U4-RXER{slash}PHYAD0)") (class "Default")
      (node (ref "R7") (pin "2") (pinfunction "2_2") (pintype "passive"))
      (node (ref "U4") (pin "10") (pinfunction "RXER/PHYAD0_10") (pintype "passive"))
    )
    (net (code "201") (name "Net-(U4-VDD1A)") (class "Default")
      (node (ref "C15") (pin "2") (pinfunction "2_2") (pintype "passive"))
      (node (ref "C21") (pin "2") (pinfunction "2_2") (pintype "passive"))
      (node (ref "C23") (pin "2") (pinfunction "2_2") (pintype "passive"))
      (node (ref "C24") (pin "2") (pinfunction "2_2") (pintype "passive"))
      (node (ref "J2") (pin "4") (pinfunction "4_4") (pintype "passive"))
      (node (ref "J2") (pin "5") (pinfunction "5_5") (pintype "passive"))
      (node (ref "L2") (pin "1") (pinfunction "1_1") (pintype "passive"))
      (node (ref "R11") (pin "2") (pinfunction "2_2") (pintype "passive"))
      (node (ref "R12") (pin "2") (pinfunction "2_2") (pintype "passive"))
      (node (ref "R14") (pin "2") (pinfunction "2_2") (pintype "passive"))
      (node (ref "R15") (pin "2") (pinfunction "2_2") (pintype "passive"))
      (node (ref "U4") (pin "1") (pinfunction "VDD2A_1") (pintype "passive"))
      (node (ref "U4") (pin "19") (pinfunction "VDD1A_19") (pintype "passive"))
    )
    (net (code "202") (name "Net-(U4-VDDCR)") (class "Default")
      (node (ref "C16") (pin "2") (pinfunction "2_2") (pintype "passive"))
      (node (ref "U4") (pin "6") (pinfunction "VDDCR_6") (pintype "passive"))
    )
    (net (code "203") (name "Net-(U4-XTAL1{slash}CLKIN)") (class "Default")
      (node (ref "C9") (pin "2") (pinfunction "2_2") (pintype "passive"))
      (node (ref "U4") (pin "5") (pinfunction "XTAL1/CLKIN_5") (pintype "passive"))
      (node (ref "X2") (pin "3") (pinfunction "X2_3") (pintype "passive"))
    )
    (net (code "204") (name "Net-(U4-XTAL2)") (class "Default")
      (node (ref "C11") (pin "2") (pinfunction "2_2") (pintype "passive"))
      (node (ref "U4") (pin "4") (pinfunction "XTAL2_4") (pintype "passive"))
      (node (ref "X2") (pin "1") (pinfunction "X1_1") (pintype "passive"))
    )
    (net (code "205") (name "Net-(U6-BOOT)") (class "Default")
      (node (ref "C28") (pin "1") (pinfunction "1_1") (pintype "passive"))
      (node (ref "U6") (pin "6") (pinfunction "BOOT_6") (pintype "passive"))
    )
    (net (code "206") (name "Net-(U6-FB)") (class "Default")
      (node (ref "C29") (pin "1") (pinfunction "1_1") (pintype "passive"))
      (node (ref "R20") (pin "2") (pinfunction "2_2") (pintype "passive"))
      (node (ref "R21") (pin "1") (pinfunction "1_1") (pintype "passive"))
      (node (ref "U6") (pin "4") (pinfunction "FB_4") (pintype "passive"))
    )
    (net (code "207") (name "Net-(U6-SW)") (class "Default")
      (node (ref "C28") (pin "2") (pinfunction "2_2") (pintype "passive"))
      (node (ref "L3") (pin "1") (pinfunction "1_1") (pintype "passive"))
      (node (ref "U6") (pin "2") (pinfunction "SW_2") (pintype "passive"))
    )
    (net (code "208") (name "unconnected-(J2-NC-Pad7)") (class "Default")
      (node (ref "J2") (pin "7") (pinfunction "NC_7") (pintype "passive"))
    )
    (net (code "209") (name "unconnected-(J5-Pad5)") (class "Default")
      (node (ref "J5") (pin "5") (pinfunction "5_5") (pintype "passive+no_connect"))
    )
    (net (code "210") (name "unconnected-(J5-Pad6)") (class "Default")
      (node (ref "J5") (pin "6") (pinfunction "6_6") (pintype "passive+no_connect"))
    )
    (net (code "211") (name "unconnected-(J5-Pad39)") (class "Default")
      (node (ref "J5") (pin "39") (pinfunction "39_39") (pintype "passive+no_connect"))
    )
    (net (code "212") (name "unconnected-(J5-Pad40)") (class "Default")
      (node (ref "J5") (pin "40") (pinfunction "40_40") (pintype "passive+no_connect"))
    )
    (net (code "213") (name "unconnected-(J5-Pad43)") (class "Default")
      (node (ref "J5") (pin "43") (pinfunction "43_43") (pintype "passive+no_connect"))
    )
    (net (code "214") (name "unconnected-(J5-Pad44)") (class "Default")
      (node (ref "J5") (pin "44") (pinfunction "44_44") (pintype "passive+no_connect"))
    )
    (net (code "215") (name "unconnected-(J5-Pad45)") (class "Default")
      (node (ref "J5") (pin "45") (pinfunction "45_45") (pintype "passive+no_connect"))
    )
    (net (code "216") (name "unconnected-(J5-Pad46)") (class "Default")
      (node (ref "J5") (pin "46") (pinfunction "46_46") (pintype "passive+no_connect"))
    )
    (net (code "217") (name "unconnected-(J5-Pad47)") (class "Default")
      (node (ref "J5") (pin "47") (pinfunction "47_47") (pintype "passive+no_connect"))
    )
    (net (code "218") (name "unconnected-(J5-Pad48)") (class "Default")
      (node (ref "J5") (pin "48") (pinfunction "48_48") (pintype "passive+no_connect"))
    )
    (net (code "219") (name "unconnected-(J5-Pad49)") (class "Default")
      (node (ref "J5") (pin "49") (pinfunction "49_49") (pintype "passive+no_connect"))
    )
    (net (code "220") (name "unconnected-(J5-Pad50)") (class "Default")
      (node (ref "J5") (pin "50") (pinfunction "50_50") (pintype "passive+no_connect"))
    )
    (net (code "221") (name "unconnected-(J5-Pad51)") (class "Default")
      (node (ref "J5") (pin "51") (pinfunction "51_51") (pintype "passive+no_connect"))
    )
    (net (code "222") (name "unconnected-(J5-Pad55)") (class "Default")
      (node (ref "J5") (pin "55") (pinfunction "55_55") (pintype "passive"))
    )
    (net (code "223") (name "unconnected-(J5-Pad56)") (class "Default")
      (node (ref "J5") (pin "56") (pinfunction "56_56") (pintype "passive"))
    )
    (net (code "224") (name "unconnected-(J6-Pad7)") (class "Default")
      (node (ref "J6") (pin "7") (pinfunction "7_7") (pintype "passive"))
    )
    (net (code "225") (name "unconnected-(J6-Pad8)") (class "Default")
      (node (ref "J6") (pin "8") (pinfunction "8_8") (pintype "passive"))
    )
    (net (code "226") (name "unconnected-(U3-NC-Pad36)") (class "Default")
      (node (ref "U3") (pin "36") (pinfunction "NC_36") (pintype "passive+no_connect"))
    )
    (net (code "227") (name "unconnected-(U3-NC-Pad40)") (class "Default")
      (node (ref "U3") (pin "40") (pinfunction "NC_40") (pintype "passive+no_connect"))
    )
    (net (code "228") (name "unconnected-(U6-EN-Pad5)") (class "Default")
      (node (ref "U6") (pin "5") (pinfunction "EN_5") (pintype "passive+no_connect"))
    )
  )
)
